# PlingPlong.net
KiCad netlist of a schematic drawn in EAGLE
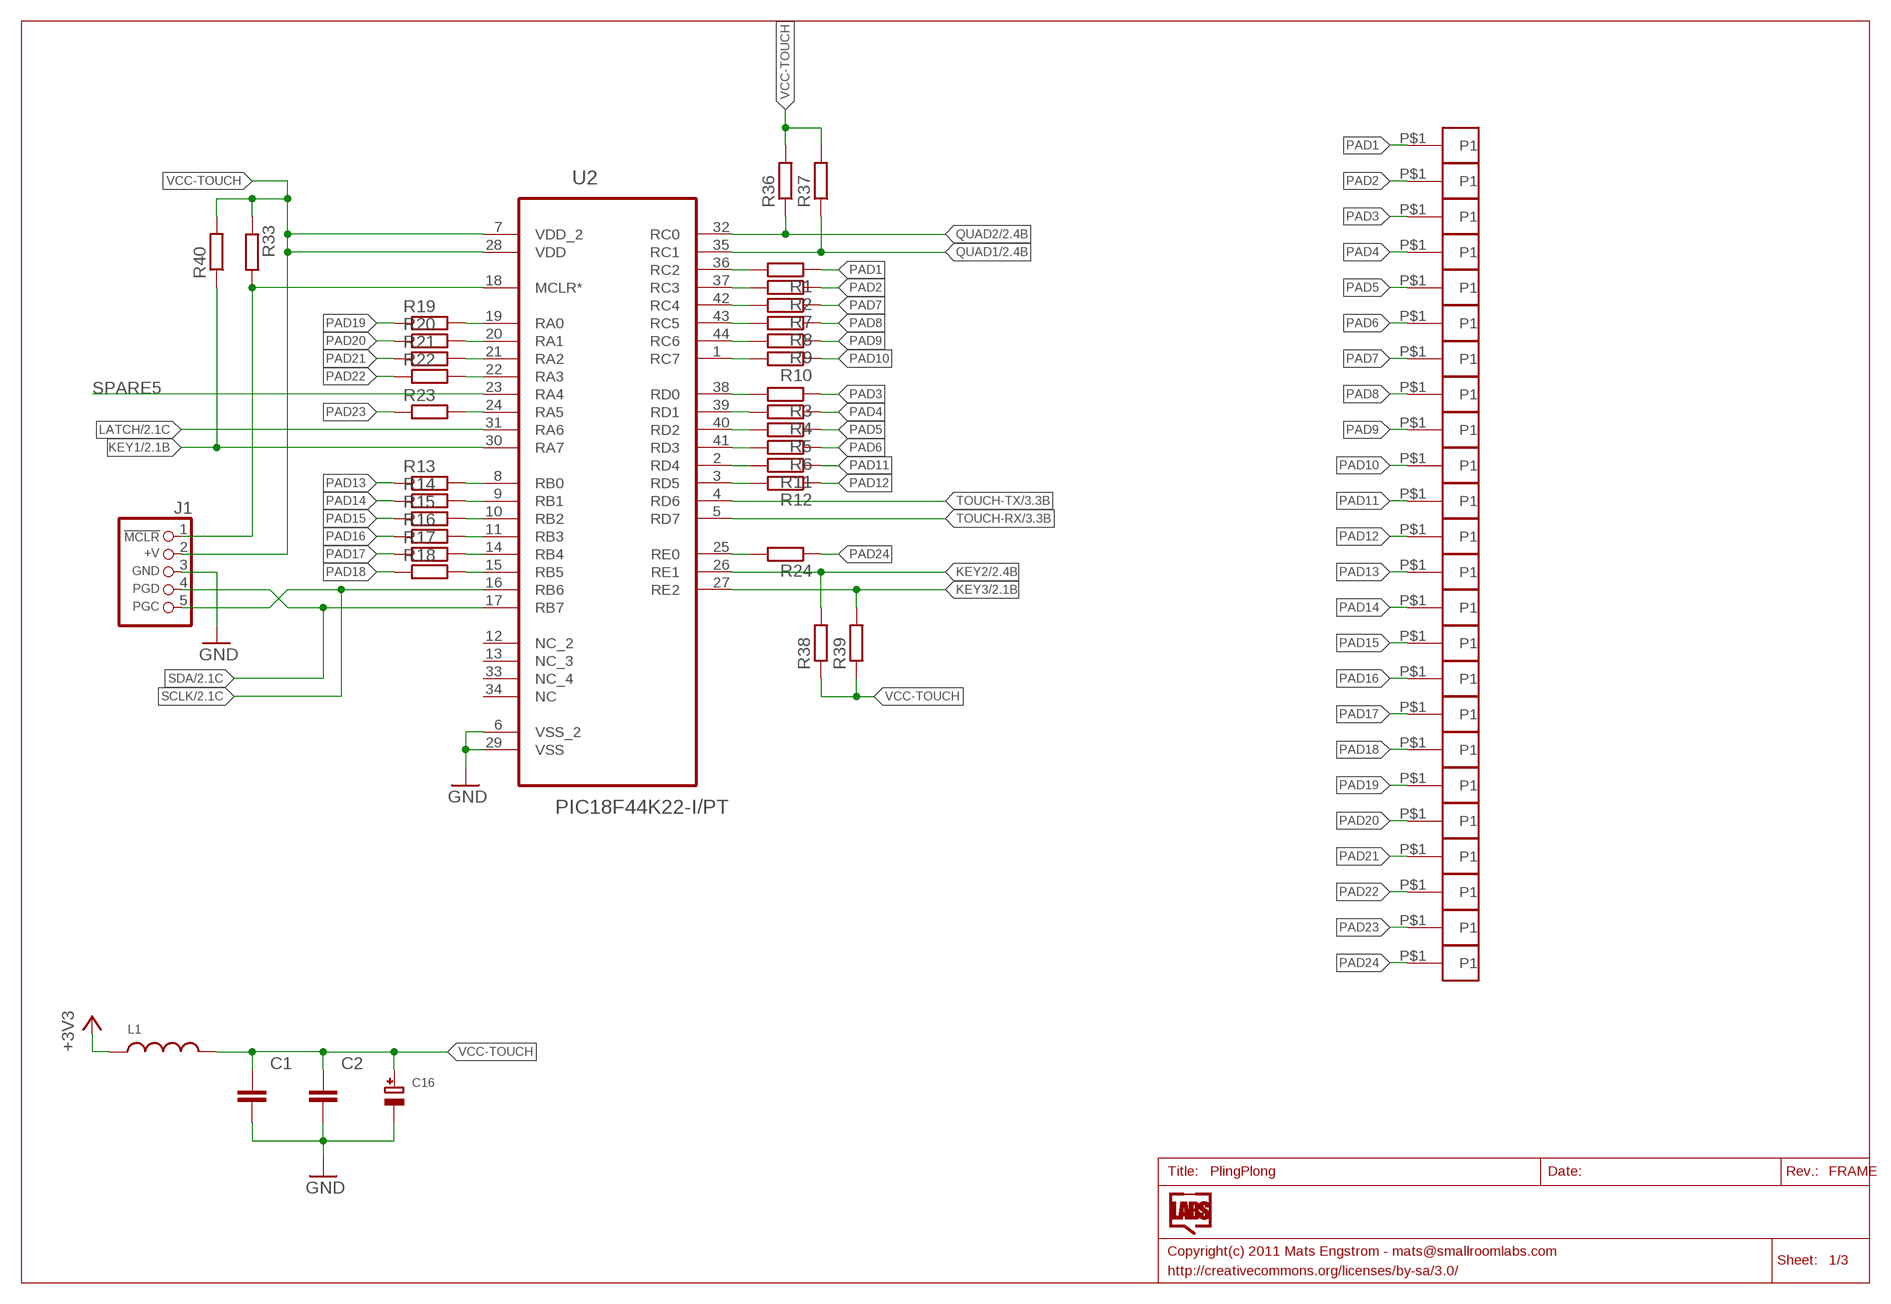
[diagram p0: schematic, sheet 1]
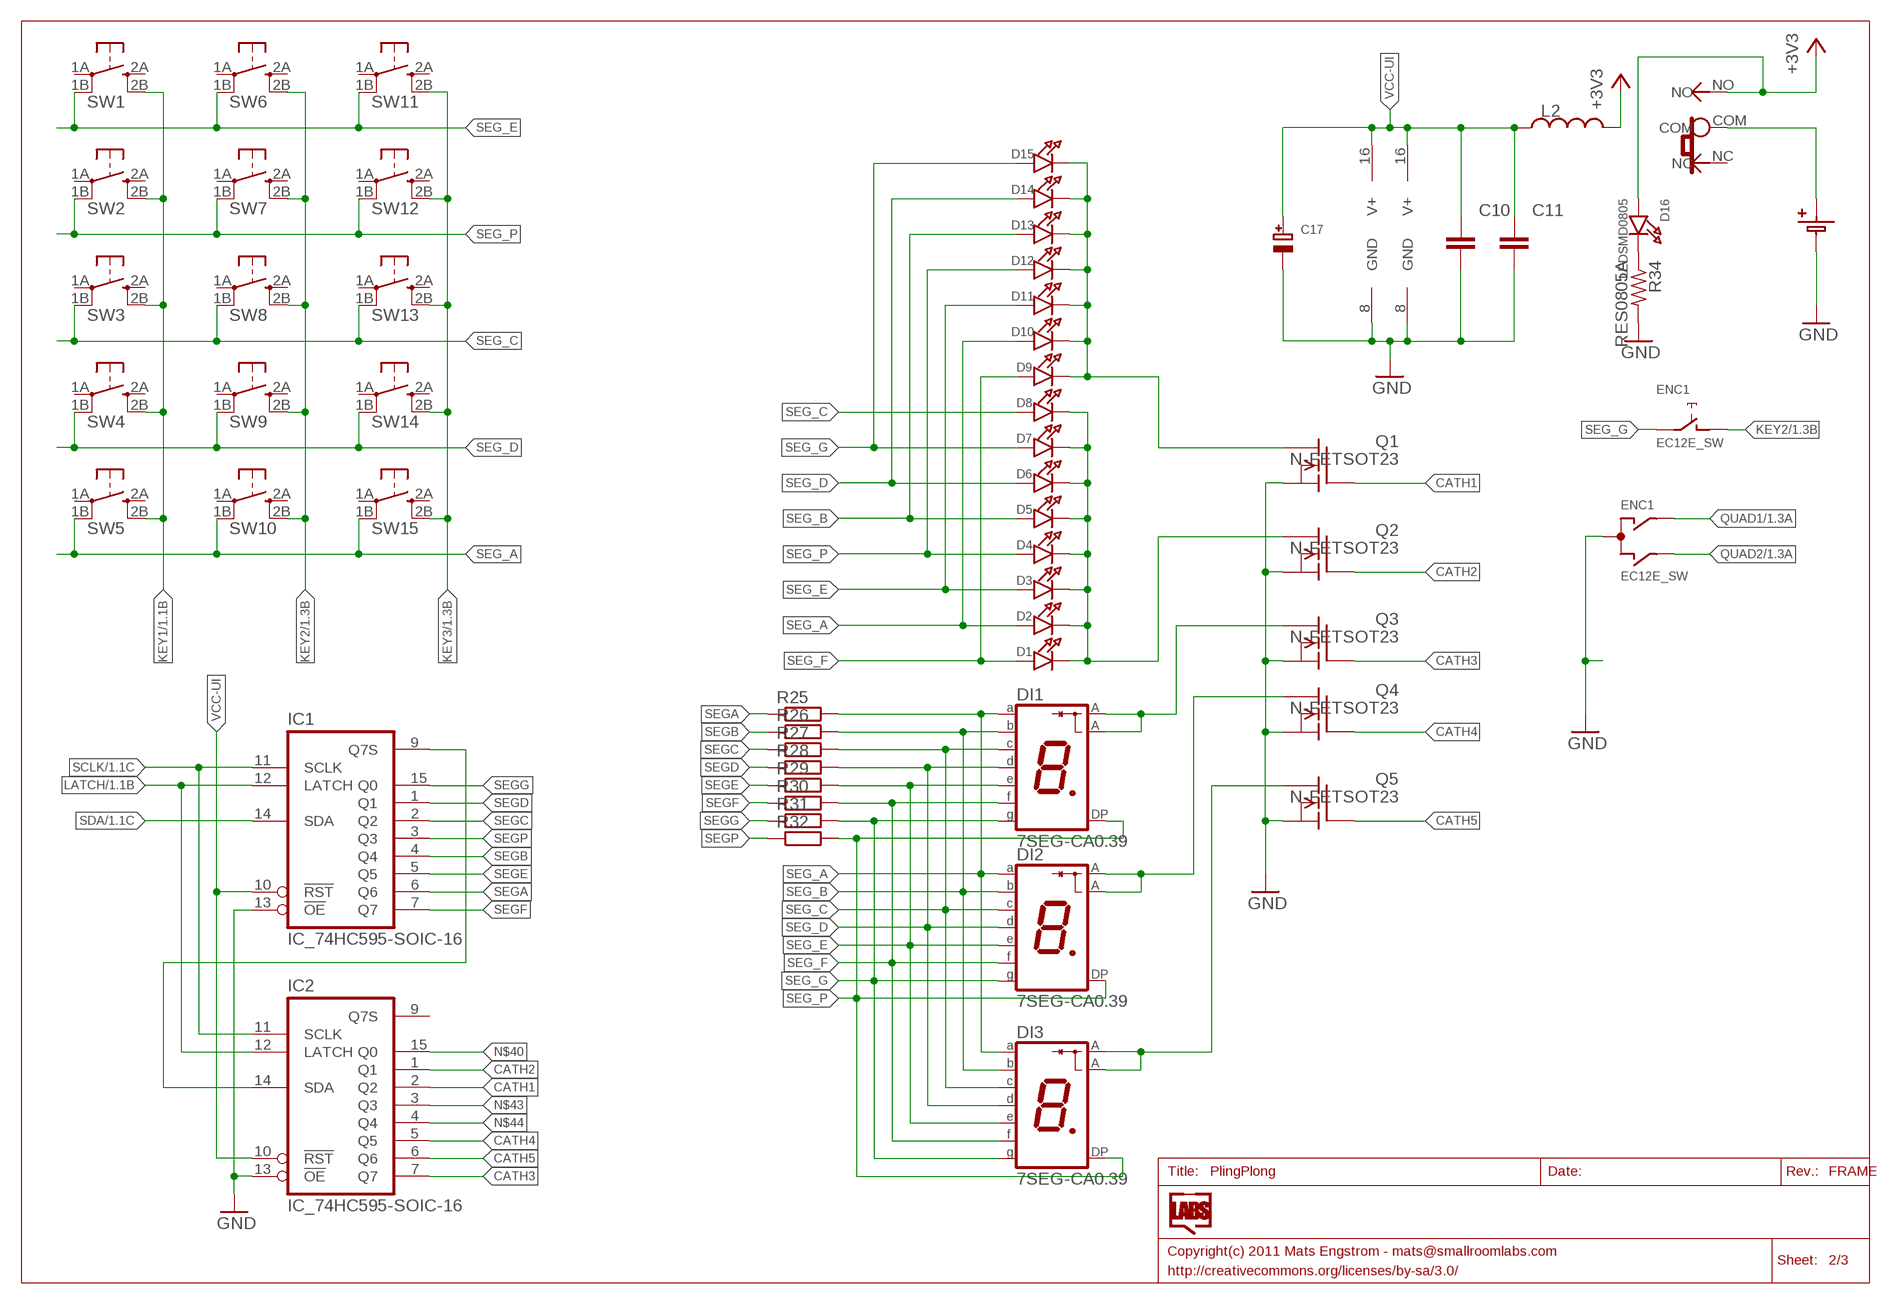
[diagram p1: schematic, sheet 2]
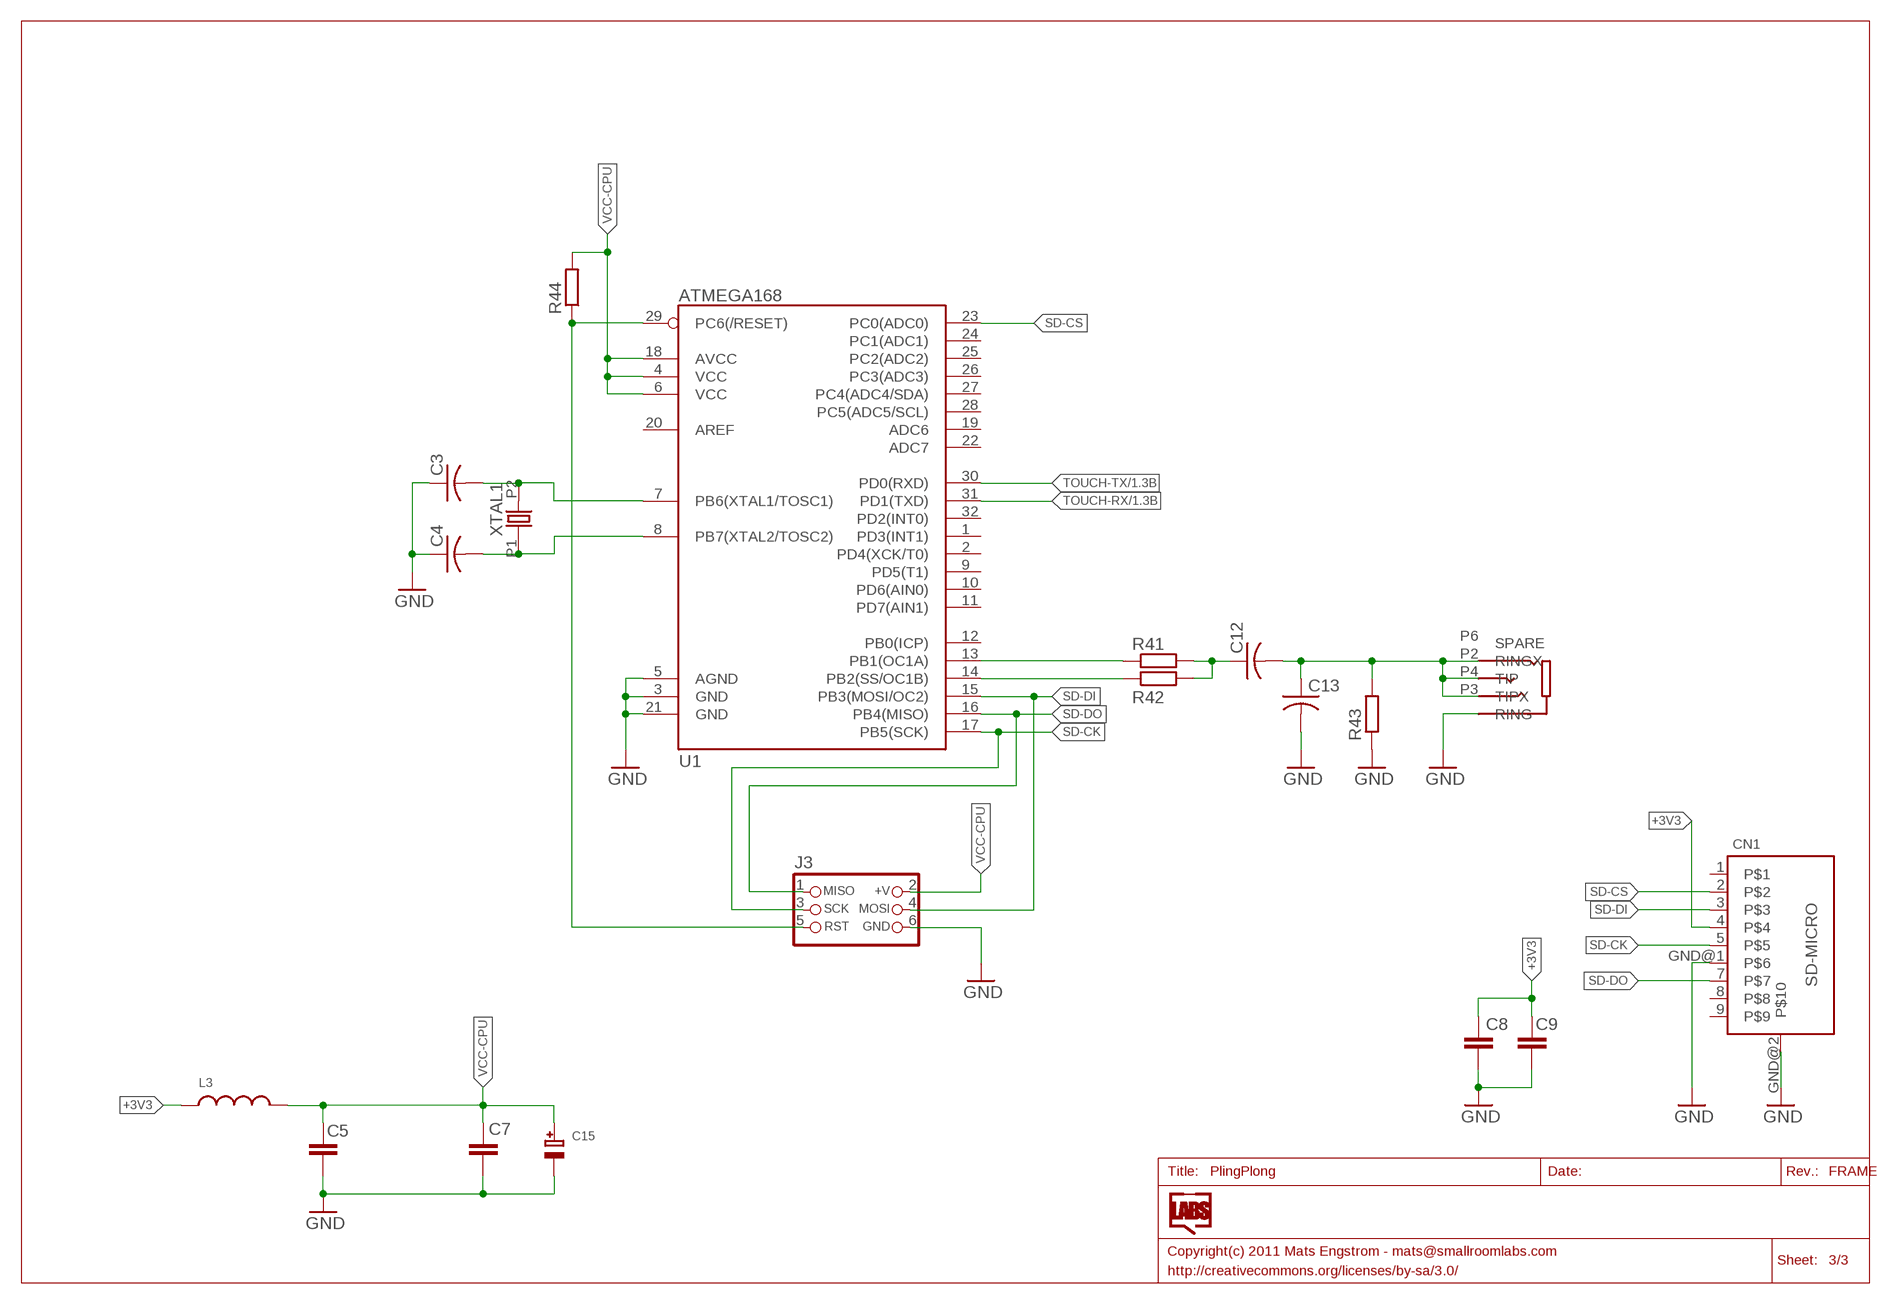
[diagram p2: schematic, sheet 3]

(export (version "E")
  (design (tool "Eeschema 10.0.6"))
  (components
    (comp (ref "C1")
      (value "CAPACITOR_NPOL-0805")
      (footprint "eagle-import:C805")
      (libsource (lib "eagle-import") (part "CAPACITOR_NPOL-0805"))
    )
    (comp (ref "C2")
      (value "CAPACITOR_NPOL-0805")
      (footprint "eagle-import:C805")
      (libsource (lib "eagle-import") (part "CAPACITOR_NPOL-0805"))
    )
    (comp (ref "C16")
      (value "CAP_TANTALUMD/7343_WAVE")
      (footprint "eagle-import:EIA7343-31_D-W")
      (libsource (lib "eagle-import") (part "CAP_TANTALUMD/7343_WAVE"))
    )
    (comp (ref "J1")
      (value "CON_HEADER_PRG_PIC_ICSPB")
      (footprint "eagle-import:HEADER_PRG_1X05_ICSP_B")
      (libsource (lib "eagle-import") (part "CON_HEADER_PRG_PIC_ICSPB"))
    )
    (comp (ref "L1")
      (value "INDUCTOR0805")
      (footprint "eagle-import:0805")
      (libsource (lib "eagle-import") (part "INDUCTOR0805"))
    )
    (comp (ref "P1")
      (value "PAD-NOSTOP")
      (footprint "eagle-import:PAD1X1NOSTOP")
      (libsource (lib "eagle-import") (part "PAD-NOSTOP"))
    )
    (comp (ref "P2")
      (value "PAD-NOSTOP")
      (footprint "eagle-import:PAD1X1NOSTOP")
      (libsource (lib "eagle-import") (part "PAD-NOSTOP"))
    )
    (comp (ref "P3")
      (value "PAD-NOSTOP")
      (footprint "eagle-import:PAD1X1NOSTOP")
      (libsource (lib "eagle-import") (part "PAD-NOSTOP"))
    )
    (comp (ref "P4")
      (value "PAD-NOSTOP")
      (footprint "eagle-import:PAD1X1NOSTOP")
      (libsource (lib "eagle-import") (part "PAD-NOSTOP"))
    )
    (comp (ref "P5")
      (value "PAD-NOSTOP")
      (footprint "eagle-import:PAD1X1NOSTOP")
      (libsource (lib "eagle-import") (part "PAD-NOSTOP"))
    )
    (comp (ref "P6")
      (value "PAD-NOSTOP")
      (footprint "eagle-import:PAD1X1NOSTOP")
      (libsource (lib "eagle-import") (part "PAD-NOSTOP"))
    )
    (comp (ref "P7")
      (value "PAD-NOSTOP")
      (footprint "eagle-import:PAD1X1NOSTOP")
      (libsource (lib "eagle-import") (part "PAD-NOSTOP"))
    )
    (comp (ref "P8")
      (value "PAD-NOSTOP")
      (footprint "eagle-import:PAD1X1NOSTOP")
      (libsource (lib "eagle-import") (part "PAD-NOSTOP"))
    )
    (comp (ref "P9")
      (value "PAD-NOSTOP")
      (footprint "eagle-import:PAD1X1NOSTOP")
      (libsource (lib "eagle-import") (part "PAD-NOSTOP"))
    )
    (comp (ref "P10")
      (value "PAD-NOSTOP")
      (footprint "eagle-import:PAD1X1NOSTOP")
      (libsource (lib "eagle-import") (part "PAD-NOSTOP"))
    )
    (comp (ref "P11")
      (value "PAD-NOSTOP")
      (footprint "eagle-import:PAD1X1NOSTOP")
      (libsource (lib "eagle-import") (part "PAD-NOSTOP"))
    )
    (comp (ref "P12")
      (value "PAD-NOSTOP")
      (footprint "eagle-import:PAD1X1NOSTOP")
      (libsource (lib "eagle-import") (part "PAD-NOSTOP"))
    )
    (comp (ref "P13")
      (value "PAD-NOSTOP")
      (footprint "eagle-import:PAD1X1NOSTOP")
      (libsource (lib "eagle-import") (part "PAD-NOSTOP"))
    )
    (comp (ref "P14")
      (value "PAD-NOSTOP")
      (footprint "eagle-import:PAD1X1NOSTOP")
      (libsource (lib "eagle-import") (part "PAD-NOSTOP"))
    )
    (comp (ref "P15")
      (value "PAD-NOSTOP")
      (footprint "eagle-import:PAD1X1NOSTOP")
      (libsource (lib "eagle-import") (part "PAD-NOSTOP"))
    )
    (comp (ref "P16")
      (value "PAD-NOSTOP")
      (footprint "eagle-import:PAD1X1NOSTOP")
      (libsource (lib "eagle-import") (part "PAD-NOSTOP"))
    )
    (comp (ref "P17")
      (value "PAD-NOSTOP")
      (footprint "eagle-import:PAD1X1NOSTOP")
      (libsource (lib "eagle-import") (part "PAD-NOSTOP"))
    )
    (comp (ref "P18")
      (value "PAD-NOSTOP")
      (footprint "eagle-import:PAD1X1NOSTOP")
      (libsource (lib "eagle-import") (part "PAD-NOSTOP"))
    )
    (comp (ref "P19")
      (value "PAD-NOSTOP")
      (footprint "eagle-import:PAD1X1NOSTOP")
      (libsource (lib "eagle-import") (part "PAD-NOSTOP"))
    )
    (comp (ref "P20")
      (value "PAD-NOSTOP")
      (footprint "eagle-import:PAD1X1NOSTOP")
      (libsource (lib "eagle-import") (part "PAD-NOSTOP"))
    )
    (comp (ref "P21")
      (value "PAD-NOSTOP")
      (footprint "eagle-import:PAD1X1NOSTOP")
      (libsource (lib "eagle-import") (part "PAD-NOSTOP"))
    )
    (comp (ref "P22")
      (value "PAD-NOSTOP")
      (footprint "eagle-import:PAD1X1NOSTOP")
      (libsource (lib "eagle-import") (part "PAD-NOSTOP"))
    )
    (comp (ref "P23")
      (value "PAD-NOSTOP")
      (footprint "eagle-import:PAD1X1NOSTOP")
      (libsource (lib "eagle-import") (part "PAD-NOSTOP"))
    )
    (comp (ref "P24")
      (value "PAD-NOSTOP")
      (footprint "eagle-import:PAD1X1NOSTOP")
      (libsource (lib "eagle-import") (part "PAD-NOSTOP"))
    )
    (comp (ref "R1")
      (value "R-EU_R0805W")
      (footprint "eagle-import:R0805W")
      (libsource (lib "eagle-import") (part "R-EU_R0805W"))
    )
    (comp (ref "R2")
      (value "R-EU_R0805W")
      (footprint "eagle-import:R0805W")
      (libsource (lib "eagle-import") (part "R-EU_R0805W"))
    )
    (comp (ref "R3")
      (value "R-EU_R0805W")
      (footprint "eagle-import:R0805W")
      (libsource (lib "eagle-import") (part "R-EU_R0805W"))
    )
    (comp (ref "R4")
      (value "R-EU_R0805W")
      (footprint "eagle-import:R0805W")
      (libsource (lib "eagle-import") (part "R-EU_R0805W"))
    )
    (comp (ref "R5")
      (value "R-EU_R0805W")
      (footprint "eagle-import:R0805W")
      (libsource (lib "eagle-import") (part "R-EU_R0805W"))
    )
    (comp (ref "R6")
      (value "R-EU_R0805W")
      (footprint "eagle-import:R0805W")
      (libsource (lib "eagle-import") (part "R-EU_R0805W"))
    )
    (comp (ref "R7")
      (value "R-EU_R0805W")
      (footprint "eagle-import:R0805W")
      (libsource (lib "eagle-import") (part "R-EU_R0805W"))
    )
    (comp (ref "R8")
      (value "R-EU_R0805W")
      (footprint "eagle-import:R0805W")
      (libsource (lib "eagle-import") (part "R-EU_R0805W"))
    )
    (comp (ref "R9")
      (value "R-EU_R0805W")
      (footprint "eagle-import:R0805W")
      (libsource (lib "eagle-import") (part "R-EU_R0805W"))
    )
    (comp (ref "R10")
      (value "R-EU_R0805W")
      (footprint "eagle-import:R0805W")
      (libsource (lib "eagle-import") (part "R-EU_R0805W"))
    )
    (comp (ref "R11")
      (value "R-EU_R0805W")
      (footprint "eagle-import:R0805W")
      (libsource (lib "eagle-import") (part "R-EU_R0805W"))
    )
    (comp (ref "R12")
      (value "R-EU_R0805W")
      (footprint "eagle-import:R0805W")
      (libsource (lib "eagle-import") (part "R-EU_R0805W"))
    )
    (comp (ref "R13")
      (value "R-EU_R0805W")
      (footprint "eagle-import:R0805W")
      (libsource (lib "eagle-import") (part "R-EU_R0805W"))
    )
    (comp (ref "R14")
      (value "R-EU_R0805W")
      (footprint "eagle-import:R0805W")
      (libsource (lib "eagle-import") (part "R-EU_R0805W"))
    )
    (comp (ref "R15")
      (value "R-EU_R0805W")
      (footprint "eagle-import:R0805W")
      (libsource (lib "eagle-import") (part "R-EU_R0805W"))
    )
    (comp (ref "R16")
      (value "R-EU_R0805W")
      (footprint "eagle-import:R0805W")
      (libsource (lib "eagle-import") (part "R-EU_R0805W"))
    )
    (comp (ref "R17")
      (value "R-EU_R0805W")
      (footprint "eagle-import:R0805W")
      (libsource (lib "eagle-import") (part "R-EU_R0805W"))
    )
    (comp (ref "R18")
      (value "R-EU_R0805W")
      (footprint "eagle-import:R0805W")
      (libsource (lib "eagle-import") (part "R-EU_R0805W"))
    )
    (comp (ref "R19")
      (value "R-EU_R0805W")
      (footprint "eagle-import:R0805W")
      (libsource (lib "eagle-import") (part "R-EU_R0805W"))
    )
    (comp (ref "R20")
      (value "R-EU_R0805W")
      (footprint "eagle-import:R0805W")
      (libsource (lib "eagle-import") (part "R-EU_R0805W"))
    )
    (comp (ref "R21")
      (value "R-EU_R0805W")
      (footprint "eagle-import:R0805W")
      (libsource (lib "eagle-import") (part "R-EU_R0805W"))
    )
    (comp (ref "R22")
      (value "R-EU_R0805W")
      (footprint "eagle-import:R0805W")
      (libsource (lib "eagle-import") (part "R-EU_R0805W"))
    )
    (comp (ref "R23")
      (value "R-EU_R0805W")
      (footprint "eagle-import:R0805W")
      (libsource (lib "eagle-import") (part "R-EU_R0805W"))
    )
    (comp (ref "R24")
      (value "R-EU_R0805W")
      (footprint "eagle-import:R0805W")
      (libsource (lib "eagle-import") (part "R-EU_R0805W"))
    )
    (comp (ref "R33")
      (value "R-EU_R0805W")
      (footprint "eagle-import:R0805W")
      (libsource (lib "eagle-import") (part "R-EU_R0805W"))
    )
    (comp (ref "R36")
      (value "R-EU_R0805W")
      (footprint "eagle-import:R0805W")
      (libsource (lib "eagle-import") (part "R-EU_R0805W"))
    )
    (comp (ref "R37")
      (value "R-EU_R0805W")
      (footprint "eagle-import:R0805W")
      (libsource (lib "eagle-import") (part "R-EU_R0805W"))
    )
    (comp (ref "R38")
      (value "R-EU_R0805W")
      (footprint "eagle-import:R0805W")
      (libsource (lib "eagle-import") (part "R-EU_R0805W"))
    )
    (comp (ref "R39")
      (value "R-EU_R0805W")
      (footprint "eagle-import:R0805W")
      (libsource (lib "eagle-import") (part "R-EU_R0805W"))
    )
    (comp (ref "R40")
      (value "R-EU_R0805W")
      (footprint "eagle-import:R0805W")
      (libsource (lib "eagle-import") (part "R-EU_R0805W"))
    )
    (comp (ref "U2")
      (value "PIC18F44K22-I/PT")
      (footprint "eagle-import:QFP80P1200X1200X120-44N")
      (libsource (lib "eagle-import") (part "PIC18F44K22-I/PT"))
    )
    (comp (ref "C3")
      (value "C-USC0805")
      (footprint "eagle-import:C0805")
      (libsource (lib "eagle-import") (part "C-USC0805"))
    )
    (comp (ref "C4")
      (value "C-USC0805")
      (footprint "eagle-import:C0805")
      (libsource (lib "eagle-import") (part "C-USC0805"))
    )
    (comp (ref "C5")
      (value "CAPACITOR_NPOL-0805")
      (footprint "eagle-import:C805")
      (libsource (lib "eagle-import") (part "CAPACITOR_NPOL-0805"))
    )
    (comp (ref "C7")
      (value "CAPACITOR_NPOL-0805")
      (footprint "eagle-import:C805")
      (libsource (lib "eagle-import") (part "CAPACITOR_NPOL-0805"))
    )
    (comp (ref "C8")
      (value "CAPACITOR_NPOL-0805")
      (footprint "eagle-import:C805")
      (libsource (lib "eagle-import") (part "CAPACITOR_NPOL-0805"))
    )
    (comp (ref "C9")
      (value "CAPACITOR_NPOL-0805")
      (footprint "eagle-import:C805")
      (libsource (lib "eagle-import") (part "CAPACITOR_NPOL-0805"))
    )
    (comp (ref "C12")
      (value "C-USC1206")
      (footprint "eagle-import:C1206")
      (libsource (lib "eagle-import") (part "C-USC1206"))
    )
    (comp (ref "C13")
      (value "C-USC0805")
      (footprint "eagle-import:C0805")
      (libsource (lib "eagle-import") (part "C-USC0805"))
    )
    (comp (ref "C15")
      (value "CAP_TANTALUMD/7343_WAVE")
      (footprint "eagle-import:EIA7343-31_D-W")
      (libsource (lib "eagle-import") (part "CAP_TANTALUMD/7343_WAVE"))
    )
    (comp (ref "CN1")
      (value "SD-MICRO")
      (footprint "eagle-import:MICROSD-TFP09")
      (libsource (lib "eagle-import") (part "SD-MICRO"))
    )
    (comp (ref "J3")
      (value "CON_HEADER_PRG_AVR_ICSP")
      (footprint "eagle-import:HEADER_PRG_2X03")
      (libsource (lib "eagle-import") (part "CON_HEADER_PRG_AVR_ICSP"))
    )
    (comp (ref "L3")
      (value "INDUCTOR0805")
      (footprint "eagle-import:0805")
      (libsource (lib "eagle-import") (part "INDUCTOR0805"))
    )
    (comp (ref "R41")
      (value "R-EU_R0805W")
      (footprint "eagle-import:R0805W")
      (libsource (lib "eagle-import") (part "R-EU_R0805W"))
    )
    (comp (ref "R42")
      (value "R-EU_R0805W")
      (footprint "eagle-import:R0805W")
      (libsource (lib "eagle-import") (part "R-EU_R0805W"))
    )
    (comp (ref "R43")
      (value "R-EU_R0805W")
      (footprint "eagle-import:R0805W")
      (libsource (lib "eagle-import") (part "R-EU_R0805W"))
    )
    (comp (ref "R44")
      (value "R-EU_R0805W")
      (footprint "eagle-import:R0805W")
      (libsource (lib "eagle-import") (part "R-EU_R0805W"))
    )
    (comp (ref "U$2")
      (value "JACK4-PJ320")
      (footprint "eagle-import:PJ-320E")
      (libsource (lib "eagle-import") (part "JACK4-PJ320"))
    )
    (comp (ref "U1")
      (value "ATMEGA168")
      (footprint "eagle-import:TQFP32-08")
      (libsource (lib "eagle-import") (part "ATMEGA168"))
    )
    (comp (ref "XTAL1")
      (value "OSC-XTAL-HC-49U-PTH")
      (footprint "eagle-import:HC-49U-PTH")
      (libsource (lib "eagle-import") (part "OSC-XTAL-HC-49U-PTH"))
    )
    (comp (ref "BA1")
      (value "BATTERY1-123PIN")
      (footprint "eagle-import:BATTERY-CR123A-PINS")
      (libsource (lib "eagle-import") (part "BATTERY1-123PIN"))
    )
    (comp (ref "C10")
      (value "CAPACITOR_NPOL-0805")
      (footprint "eagle-import:C805")
      (libsource (lib "eagle-import") (part "CAPACITOR_NPOL-0805"))
    )
    (comp (ref "C11")
      (value "CAPACITOR_NPOL-0805")
      (footprint "eagle-import:C805")
      (libsource (lib "eagle-import") (part "CAPACITOR_NPOL-0805"))
    )
    (comp (ref "C17")
      (value "CAP_TANTALUMD/7343_WAVE")
      (footprint "eagle-import:EIA7343-31_D-W")
      (libsource (lib "eagle-import") (part "CAP_TANTALUMD/7343_WAVE"))
    )
    (comp (ref "D1")
      (value "LED3MM")
      (footprint "eagle-import:LED3MM")
      (libsource (lib "eagle-import") (part "LED3MM"))
    )
    (comp (ref "D2")
      (value "LED3MM")
      (footprint "eagle-import:LED3MM")
      (libsource (lib "eagle-import") (part "LED3MM"))
    )
    (comp (ref "D3")
      (value "LED3MM")
      (footprint "eagle-import:LED3MM")
      (libsource (lib "eagle-import") (part "LED3MM"))
    )
    (comp (ref "D4")
      (value "LED3MM")
      (footprint "eagle-import:LED3MM")
      (libsource (lib "eagle-import") (part "LED3MM"))
    )
    (comp (ref "D5")
      (value "LED3MM")
      (footprint "eagle-import:LED3MM")
      (libsource (lib "eagle-import") (part "LED3MM"))
    )
    (comp (ref "D6")
      (value "LED3MM")
      (footprint "eagle-import:LED3MM")
      (libsource (lib "eagle-import") (part "LED3MM"))
    )
    (comp (ref "D7")
      (value "LED3MM")
      (footprint "eagle-import:LED3MM")
      (libsource (lib "eagle-import") (part "LED3MM"))
    )
    (comp (ref "D8")
      (value "LED3MM")
      (footprint "eagle-import:LED3MM")
      (libsource (lib "eagle-import") (part "LED3MM"))
    )
    (comp (ref "D9")
      (value "LED3MM")
      (footprint "eagle-import:LED3MM")
      (libsource (lib "eagle-import") (part "LED3MM"))
    )
    (comp (ref "D10")
      (value "LED3MM")
      (footprint "eagle-import:LED3MM")
      (libsource (lib "eagle-import") (part "LED3MM"))
    )
    (comp (ref "D11")
      (value "LED3MM")
      (footprint "eagle-import:LED3MM")
      (libsource (lib "eagle-import") (part "LED3MM"))
    )
    (comp (ref "D12")
      (value "LED3MM")
      (footprint "eagle-import:LED3MM")
      (libsource (lib "eagle-import") (part "LED3MM"))
    )
    (comp (ref "D13")
      (value "LED3MM")
      (footprint "eagle-import:LED3MM")
      (libsource (lib "eagle-import") (part "LED3MM"))
    )
    (comp (ref "D14")
      (value "LED3MM")
      (footprint "eagle-import:LED3MM")
      (libsource (lib "eagle-import") (part "LED3MM"))
    )
    (comp (ref "D15")
      (value "LED3MM")
      (footprint "eagle-import:LED3MM")
      (libsource (lib "eagle-import") (part "LED3MM"))
    )
    (comp (ref "D16")
      (value "LEDSMD0805")
      (footprint "eagle-import:CHIPLED_0805")
      (libsource (lib "eagle-import") (part "LEDSMD0805"))
    )
    (comp (ref "DI1")
      (value "7SEG-CA0.39")
      (footprint "eagle-import:LG3911")
      (libsource (lib "eagle-import") (part "7SEG-CA0.39"))
    )
    (comp (ref "DI2")
      (value "7SEG-CA0.39")
      (footprint "eagle-import:LG3911")
      (libsource (lib "eagle-import") (part "7SEG-CA0.39"))
    )
    (comp (ref "DI3")
      (value "7SEG-CA0.39")
      (footprint "eagle-import:LG3911")
      (libsource (lib "eagle-import") (part "7SEG-CA0.39"))
    )
    (comp (ref "ENC1")
      (value "EC12E_SW")
      (footprint "eagle-import:ALPS_EC12E_SW")
      (fields (field (name "MPN") "EC12E2424407"))
      (libsource (lib "eagle-import") (part "EC12E_SW"))
    )
    (comp (ref "IC1")
      (value "IC_74HC595-SOIC-16")
      (footprint "eagle-import:SOIC-16")
      (libsource (lib "eagle-import") (part "IC_74HC595-SOIC-16"))
    )
    (comp (ref "IC2")
      (value "IC_74HC595-SOIC-16")
      (footprint "eagle-import:SOIC-16")
      (libsource (lib "eagle-import") (part "IC_74HC595-SOIC-16"))
    )
    (comp (ref "L2")
      (value "INDUCTOR0805")
      (footprint "eagle-import:0805")
      (libsource (lib "eagle-import") (part "INDUCTOR0805"))
    )
    (comp (ref "Q1")
      (value "N-FETSOT23")
      (footprint "eagle-import:SOT23")
      (libsource (lib "eagle-import") (part "N-FETSOT23"))
    )
    (comp (ref "Q2")
      (value "N-FETSOT23")
      (footprint "eagle-import:SOT23")
      (libsource (lib "eagle-import") (part "N-FETSOT23"))
    )
    (comp (ref "Q3")
      (value "N-FETSOT23")
      (footprint "eagle-import:SOT23")
      (libsource (lib "eagle-import") (part "N-FETSOT23"))
    )
    (comp (ref "Q4")
      (value "N-FETSOT23")
      (footprint "eagle-import:SOT23")
      (libsource (lib "eagle-import") (part "N-FETSOT23"))
    )
    (comp (ref "Q5")
      (value "N-FETSOT23")
      (footprint "eagle-import:SOT23")
      (libsource (lib "eagle-import") (part "N-FETSOT23"))
    )
    (comp (ref "R25")
      (value "R-EU_R0805W")
      (footprint "eagle-import:R0805W")
      (libsource (lib "eagle-import") (part "R-EU_R0805W"))
    )
    (comp (ref "R26")
      (value "R-EU_R0805W")
      (footprint "eagle-import:R0805W")
      (libsource (lib "eagle-import") (part "R-EU_R0805W"))
    )
    (comp (ref "R27")
      (value "R-EU_R0805W")
      (footprint "eagle-import:R0805W")
      (libsource (lib "eagle-import") (part "R-EU_R0805W"))
    )
    (comp (ref "R28")
      (value "R-EU_R0805W")
      (footprint "eagle-import:R0805W")
      (libsource (lib "eagle-import") (part "R-EU_R0805W"))
    )
    (comp (ref "R29")
      (value "R-EU_R0805W")
      (footprint "eagle-import:R0805W")
      (libsource (lib "eagle-import") (part "R-EU_R0805W"))
    )
    (comp (ref "R30")
      (value "R-EU_R0805W")
      (footprint "eagle-import:R0805W")
      (libsource (lib "eagle-import") (part "R-EU_R0805W"))
    )
    (comp (ref "R31")
      (value "R-EU_R0805W")
      (footprint "eagle-import:R0805W")
      (libsource (lib "eagle-import") (part "R-EU_R0805W"))
    )
    (comp (ref "R32")
      (value "R-EU_R0805W")
      (footprint "eagle-import:R0805W")
      (libsource (lib "eagle-import") (part "R-EU_R0805W"))
    )
    (comp (ref "R34")
      (value "RES0805A")
      (footprint "eagle-import:R0805A")
      (libsource (lib "eagle-import") (part "RES0805A"))
    )
    (comp (ref "SW1")
      (value "TACTILETACT-6X6-PTH")
      (footprint "eagle-import:TACTILE-PTH")
      (libsource (lib "eagle-import") (part "TACTILETACT-6X6-PTH"))
    )
    (comp (ref "SW2")
      (value "TACTILETACT-6X6-PTH")
      (footprint "eagle-import:TACTILE-PTH")
      (libsource (lib "eagle-import") (part "TACTILETACT-6X6-PTH"))
    )
    (comp (ref "SW3")
      (value "TACTILETACT-6X6-PTH")
      (footprint "eagle-import:TACTILE-PTH")
      (libsource (lib "eagle-import") (part "TACTILETACT-6X6-PTH"))
    )
    (comp (ref "SW4")
      (value "TACTILETACT-6X6-PTH")
      (footprint "eagle-import:TACTILE-PTH")
      (libsource (lib "eagle-import") (part "TACTILETACT-6X6-PTH"))
    )
    (comp (ref "SW5")
      (value "TACTILETACT-6X6-PTH")
      (footprint "eagle-import:TACTILE-PTH")
      (libsource (lib "eagle-import") (part "TACTILETACT-6X6-PTH"))
    )
    (comp (ref "SW6")
      (value "TACTILETACT-6X6-PTH")
      (footprint "eagle-import:TACTILE-PTH")
      (libsource (lib "eagle-import") (part "TACTILETACT-6X6-PTH"))
    )
    (comp (ref "SW7")
      (value "TACTILETACT-6X6-PTH")
      (footprint "eagle-import:TACTILE-PTH")
      (libsource (lib "eagle-import") (part "TACTILETACT-6X6-PTH"))
    )
    (comp (ref "SW8")
      (value "TACTILETACT-6X6-PTH")
      (footprint "eagle-import:TACTILE-PTH")
      (libsource (lib "eagle-import") (part "TACTILETACT-6X6-PTH"))
    )
    (comp (ref "SW9")
      (value "TACTILETACT-6X6-PTH")
      (footprint "eagle-import:TACTILE-PTH")
      (libsource (lib "eagle-import") (part "TACTILETACT-6X6-PTH"))
    )
    (comp (ref "SW10")
      (value "TACTILETACT-6X6-PTH")
      (footprint "eagle-import:TACTILE-PTH")
      (libsource (lib "eagle-import") (part "TACTILETACT-6X6-PTH"))
    )
    (comp (ref "SW11")
      (value "TACTILETACT-6X6-PTH")
      (footprint "eagle-import:TACTILE-PTH")
      (libsource (lib "eagle-import") (part "TACTILETACT-6X6-PTH"))
    )
    (comp (ref "SW12")
      (value "TACTILETACT-6X6-PTH")
      (footprint "eagle-import:TACTILE-PTH")
      (libsource (lib "eagle-import") (part "TACTILETACT-6X6-PTH"))
    )
    (comp (ref "SW13")
      (value "TACTILETACT-6X6-PTH")
      (footprint "eagle-import:TACTILE-PTH")
      (libsource (lib "eagle-import") (part "TACTILETACT-6X6-PTH"))
    )
    (comp (ref "SW14")
      (value "TACTILETACT-6X6-PTH")
      (footprint "eagle-import:TACTILE-PTH")
      (libsource (lib "eagle-import") (part "TACTILETACT-6X6-PTH"))
    )
    (comp (ref "SW15")
      (value "TACTILETACT-6X6-PTH")
      (footprint "eagle-import:TACTILE-PTH")
      (libsource (lib "eagle-import") (part "TACTILETACT-6X6-PTH"))
    )
    (comp (ref "SW16")
      (value "SLIDESWITCH-PCM12")
      (footprint "eagle-import:PCM12")
      (libsource (lib "eagle-import") (part "SLIDESWITCH-PCM12"))
    )
  )
  (nets
    (net (code "1") (name "+3V3") (class "Default")
      (node (ref "C8") (pin "1") (pinfunction "1_1") (pintype "passive"))
      (node (ref "C9") (pin "1") (pinfunction "1_1") (pintype "passive"))
      (node (ref "CN1") (pin "4") (pinfunction "P$4_4") (pintype "bidirectional"))
      (node (ref "D16") (pin "A") (pinfunction "A_A") (pintype "passive"))
      (node (ref "L1") (pin "1") (pinfunction "1_1") (pintype "passive"))
      (node (ref "L2") (pin "2") (pinfunction "2_2") (pintype "passive"))
      (node (ref "L3") (pin "1") (pinfunction "1_1") (pintype "passive"))
      (node (ref "SW16") (pin "NO") (pinfunction "NO_NO") (pintype "bidirectional"))
    )
    (net (code "2") (name "CATH1") (class "Default")
      (node (ref "IC2") (pin "2") (pinfunction "Q2_2") (pintype "output"))
      (node (ref "Q1") (pin "1") (pinfunction "G_1") (pintype "passive"))
    )
    (net (code "3") (name "CATH2") (class "Default")
      (node (ref "IC2") (pin "1") (pinfunction "Q1_1") (pintype "output"))
      (node (ref "Q2") (pin "1") (pinfunction "G_1") (pintype "passive"))
    )
    (net (code "4") (name "CATH3") (class "Default")
      (node (ref "IC2") (pin "7") (pinfunction "Q7_7") (pintype "output"))
      (node (ref "Q3") (pin "1") (pinfunction "G_1") (pintype "passive"))
    )
    (net (code "5") (name "CATH4") (class "Default")
      (node (ref "IC2") (pin "5") (pinfunction "Q5_5") (pintype "output"))
      (node (ref "Q4") (pin "1") (pinfunction "G_1") (pintype "passive"))
    )
    (net (code "6") (name "CATH5") (class "Default")
      (node (ref "IC2") (pin "6") (pinfunction "Q6_6") (pintype "output"))
      (node (ref "Q5") (pin "1") (pinfunction "G_1") (pintype "passive"))
    )
    (net (code "7") (name "GND") (class "Default")
      (node (ref "BA1") (pin "NEG") (pinfunction "NEG_NEG") (pintype "power_in"))
      (node (ref "C1") (pin "2") (pinfunction "2_2") (pintype "passive"))
      (node (ref "C10") (pin "2") (pinfunction "2_2") (pintype "passive"))
      (node (ref "C11") (pin "2") (pinfunction "2_2") (pintype "passive"))
      (node (ref "C13") (pin "2") (pinfunction "2_2") (pintype "passive"))
      (node (ref "C15") (pin "-") (pinfunction "-_-") (pintype "passive"))
      (node (ref "C16") (pin "-") (pinfunction "-_-") (pintype "passive"))
      (node (ref "C17") (pin "-") (pinfunction "-_-") (pintype "passive"))
      (node (ref "C2") (pin "2") (pinfunction "2_2") (pintype "passive"))
      (node (ref "C3") (pin "1") (pinfunction "1_1") (pintype "passive"))
      (node (ref "C4") (pin "1") (pinfunction "1_1") (pintype "passive"))
      (node (ref "C5") (pin "2") (pinfunction "2_2") (pintype "passive"))
      (node (ref "C7") (pin "2") (pinfunction "2_2") (pintype "passive"))
      (node (ref "C8") (pin "2") (pinfunction "2_2") (pintype "passive"))
      (node (ref "C9") (pin "2") (pinfunction "2_2") (pintype "passive"))
      (node (ref "CN1") (pin "GND@1") (pinfunction "P$6_GND@1") (pintype "bidirectional"))
      (node (ref "CN1") (pin "GND@2") (pinfunction "P$10_GND@2") (pintype "bidirectional"))
      (node (ref "ENC1") (pin "C") (pinfunction "C_C") (pintype "passive"))
      (node (ref "IC1") (pin "13") (pinfunction "~{OE}_13") (pintype "input"))
      (node (ref "IC1") (pin "8") (pinfunction "GND_8") (pintype "power_in"))
      (node (ref "IC2") (pin "13") (pinfunction "~{OE}_13") (pintype "input"))
      (node (ref "IC2") (pin "8") (pinfunction "GND_8") (pintype "power_in"))
      (node (ref "J1") (pin "3") (pinfunction "GND_3") (pintype "passive"))
      (node (ref "J3") (pin "6") (pinfunction "GND_6") (pintype "passive"))
      (node (ref "Q1") (pin "2") (pinfunction "S_2") (pintype "passive"))
      (node (ref "Q2") (pin "2") (pinfunction "S_2") (pintype "passive"))
      (node (ref "Q3") (pin "2") (pinfunction "S_2") (pintype "passive"))
      (node (ref "Q4") (pin "2") (pinfunction "S_2") (pintype "passive"))
      (node (ref "Q5") (pin "2") (pinfunction "S_2") (pintype "passive"))
      (node (ref "R34") (pin "2") (pinfunction "2_2") (pintype "passive"))
      (node (ref "R43") (pin "1") (pinfunction "1_1") (pintype "passive"))
      (node (ref "U$2") (pin "P5") (pinfunction "RING_P5") (pintype "bidirectional"))
      (node (ref "U1") (pin "21") (pinfunction "GND_21") (pintype "bidirectional"))
      (node (ref "U1") (pin "3") (pinfunction "GND_3") (pintype "bidirectional"))
      (node (ref "U1") (pin "5") (pinfunction "AGND_5") (pintype "bidirectional"))
      (node (ref "U2") (pin "29") (pinfunction "VSS_29") (pintype "power_in"))
      (node (ref "U2") (pin "6") (pinfunction "VSS_2_6") (pintype "power_in"))
    )
    (net (code "8") (name "KEY1") (class "Default")
      (node (ref "R40") (pin "1") (pinfunction "1_1") (pintype "passive"))
      (node (ref "SW1") (pin "2B") (pinfunction "2B_2B") (pintype "passive"))
      (node (ref "SW2") (pin "2B") (pinfunction "2B_2B") (pintype "passive"))
      (node (ref "SW3") (pin "2B") (pinfunction "2B_2B") (pintype "passive"))
      (node (ref "SW4") (pin "2B") (pinfunction "2B_2B") (pintype "passive"))
      (node (ref "SW5") (pin "2B") (pinfunction "2B_2B") (pintype "passive"))
      (node (ref "U2") (pin "30") (pinfunction "RA7_30") (pintype "bidirectional"))
    )
    (net (code "9") (name "KEY2") (class "Default")
      (node (ref "ENC1") (pin "D") (pinfunction "1_D") (pintype "passive"))
      (node (ref "R38") (pin "2") (pinfunction "2_2") (pintype "passive"))
      (node (ref "SW10") (pin "2B") (pinfunction "2B_2B") (pintype "passive"))
      (node (ref "SW6") (pin "2B") (pinfunction "2B_2B") (pintype "passive"))
      (node (ref "SW7") (pin "2B") (pinfunction "2B_2B") (pintype "passive"))
      (node (ref "SW8") (pin "2B") (pinfunction "2B_2B") (pintype "passive"))
      (node (ref "SW9") (pin "2B") (pinfunction "2B_2B") (pintype "passive"))
      (node (ref "U2") (pin "26") (pinfunction "RE1_26") (pintype "bidirectional"))
    )
    (net (code "10") (name "KEY3") (class "Default")
      (node (ref "R39") (pin "2") (pinfunction "2_2") (pintype "passive"))
      (node (ref "SW11") (pin "2B") (pinfunction "2B_2B") (pintype "passive"))
      (node (ref "SW12") (pin "2B") (pinfunction "2B_2B") (pintype "passive"))
      (node (ref "SW13") (pin "2B") (pinfunction "2B_2B") (pintype "passive"))
      (node (ref "SW14") (pin "2B") (pinfunction "2B_2B") (pintype "passive"))
      (node (ref "SW15") (pin "2B") (pinfunction "2B_2B") (pintype "passive"))
      (node (ref "U2") (pin "27") (pinfunction "RE2_27") (pintype "bidirectional"))
    )
    (net (code "11") (name "LATCH") (class "Default")
      (node (ref "IC1") (pin "12") (pinfunction "LATCH_12") (pintype "input"))
      (node (ref "IC2") (pin "12") (pinfunction "LATCH_12") (pintype "input"))
      (node (ref "U2") (pin "31") (pinfunction "RA6_31") (pintype "bidirectional"))
    )
    (net (code "12") (name "N$40") (class "Default")
      (node (ref "IC2") (pin "15") (pinfunction "Q0_15") (pintype "output"))
    )
    (net (code "13") (name "N$43") (class "Default")
      (node (ref "IC2") (pin "3") (pinfunction "Q3_3") (pintype "output"))
    )
    (net (code "14") (name "N$44") (class "Default")
      (node (ref "IC2") (pin "4") (pinfunction "Q4_4") (pintype "output"))
    )
    (net (code "15") (name "Net-(BA1-POS1)") (class "Default")
      (node (ref "BA1") (pin "POS") (pinfunction "POS1_POS") (pintype "power_in"))
      (node (ref "SW16") (pin "COM") (pinfunction "COM_COM") (pintype "bidirectional"))
    )
    (net (code "16") (name "Net-(C12-Pad1)") (class "Default")
      (node (ref "C12") (pin "1") (pinfunction "1_1") (pintype "passive"))
      (node (ref "R41") (pin "2") (pinfunction "2_2") (pintype "passive"))
      (node (ref "R42") (pin "2") (pinfunction "2_2") (pintype "passive"))
    )
    (net (code "17") (name "Net-(D16-PadC)") (class "Default")
      (node (ref "D16") (pin "C") (pinfunction "C_C") (pintype "passive"))
      (node (ref "R34") (pin "1") (pinfunction "1_1") (pintype "passive"))
    )
    (net (code "18") (name "Net-(IC1A-Q7S)") (class "Default")
      (node (ref "IC1") (pin "9") (pinfunction "Q7S_9") (pintype "output"))
      (node (ref "IC2") (pin "14") (pinfunction "SDA_14") (pintype "input"))
    )
    (net (code "19") (name "Net-(J1-{slash}MCLR)") (class "Default")
      (node (ref "J1") (pin "1") (pinfunction "/MCLR_1") (pintype "passive"))
      (node (ref "R33") (pin "2") (pinfunction "2_2") (pintype "passive"))
      (node (ref "U2") (pin "18") (pinfunction "MCLR*_18") (pintype "input"))
    )
    (net (code "20") (name "Net-(J3-RST)") (class "Default")
      (node (ref "J3") (pin "5") (pinfunction "RST_5") (pintype "passive"))
      (node (ref "R44") (pin "1") (pinfunction "1_1") (pintype "passive"))
      (node (ref "U1") (pin "29") (pinfunction "PC6(/RESET)_29") (pintype "bidirectional"))
    )
    (net (code "21") (name "Net-(Q1-D)") (class "Default")
      (node (ref "D10") (pin "C") (pinfunction "C_C") (pintype "passive"))
      (node (ref "D11") (pin "C") (pinfunction "C_C") (pintype "passive"))
      (node (ref "D12") (pin "C") (pinfunction "C_C") (pintype "passive"))
      (node (ref "D13") (pin "C") (pinfunction "C_C") (pintype "passive"))
      (node (ref "D14") (pin "C") (pinfunction "C_C") (pintype "passive"))
      (node (ref "D15") (pin "C") (pinfunction "C_C") (pintype "passive"))
      (node (ref "D9") (pin "C") (pinfunction "C_C") (pintype "passive"))
      (node (ref "Q1") (pin "3") (pinfunction "D_3") (pintype "passive"))
    )
    (net (code "22") (name "Net-(Q2-D)") (class "Default")
      (node (ref "D1") (pin "C") (pinfunction "C_C") (pintype "passive"))
      (node (ref "D2") (pin "C") (pinfunction "C_C") (pintype "passive"))
      (node (ref "D3") (pin "C") (pinfunction "C_C") (pintype "passive"))
      (node (ref "D4") (pin "C") (pinfunction "C_C") (pintype "passive"))
      (node (ref "D5") (pin "C") (pinfunction "C_C") (pintype "passive"))
      (node (ref "D6") (pin "C") (pinfunction "C_C") (pintype "passive"))
      (node (ref "D7") (pin "C") (pinfunction "C_C") (pintype "passive"))
      (node (ref "D8") (pin "C") (pinfunction "C_C") (pintype "passive"))
      (node (ref "Q2") (pin "3") (pinfunction "D_3") (pintype "passive"))
    )
    (net (code "23") (name "Net-(Q3-D)") (class "Default")
      (node (ref "DI1") (pin "P$3") (pinfunction "A_P$3") (pintype "passive"))
      (node (ref "DI1") (pin "P$8") (pinfunction "A_P$8") (pintype "passive"))
      (node (ref "Q3") (pin "3") (pinfunction "D_3") (pintype "passive"))
    )
    (net (code "24") (name "Net-(Q4-D)") (class "Default")
      (node (ref "DI2") (pin "P$3") (pinfunction "A_P$3") (pintype "passive"))
      (node (ref "DI2") (pin "P$8") (pinfunction "A_P$8") (pintype "passive"))
      (node (ref "Q4") (pin "3") (pinfunction "D_3") (pintype "passive"))
    )
    (net (code "25") (name "Net-(Q5-D)") (class "Default")
      (node (ref "DI3") (pin "P$3") (pinfunction "A_P$3") (pintype "passive"))
      (node (ref "DI3") (pin "P$8") (pinfunction "A_P$8") (pintype "passive"))
      (node (ref "Q5") (pin "3") (pinfunction "D_3") (pintype "passive"))
    )
    (net (code "26") (name "Net-(U$2-RINGX)") (class "Default")
      (node (ref "C12") (pin "2") (pinfunction "2_2") (pintype "passive"))
      (node (ref "C13") (pin "1") (pinfunction "1_1") (pintype "passive"))
      (node (ref "R43") (pin "2") (pinfunction "2_2") (pintype "passive"))
      (node (ref "U$2") (pin "P2") (pinfunction "RINGX_P2") (pintype "bidirectional"))
      (node (ref "U$2") (pin "P3") (pinfunction "TIPX_P3") (pintype "bidirectional"))
      (node (ref "U$2") (pin "P4") (pinfunction "TIP_P4") (pintype "bidirectional"))
    )
    (net (code "27") (name "Net-(U1-PB1(OC1A))") (class "Default")
      (node (ref "R41") (pin "1") (pinfunction "1_1") (pintype "passive"))
      (node (ref "U1") (pin "13") (pinfunction "PB1(OC1A)_13") (pintype "bidirectional"))
    )
    (net (code "28") (name "Net-(U1-PB2(SS{slash}OC1B))") (class "Default")
      (node (ref "R42") (pin "1") (pinfunction "1_1") (pintype "passive"))
      (node (ref "U1") (pin "14") (pinfunction "PB2(SS/OC1B)_14") (pintype "bidirectional"))
    )
    (net (code "29") (name "Net-(U1-PB6(XTAL1{slash}TOSC1))") (class "Default")
      (node (ref "C3") (pin "2") (pinfunction "2_2") (pintype "passive"))
      (node (ref "U1") (pin "7") (pinfunction "PB6(XTAL1/TOSC1)_7") (pintype "bidirectional"))
      (node (ref "XTAL1") (pin "P2") (pinfunction "2_P2") (pintype "passive"))
    )
    (net (code "30") (name "Net-(U1-PB7(XTAL2{slash}TOSC2))") (class "Default")
      (node (ref "C4") (pin "2") (pinfunction "2_2") (pintype "passive"))
      (node (ref "U1") (pin "8") (pinfunction "PB7(XTAL2/TOSC2)_8") (pintype "bidirectional"))
      (node (ref "XTAL1") (pin "P1") (pinfunction "1_P1") (pintype "passive"))
    )
    (net (code "31") (name "Net-(U2-RA0)") (class "Default")
      (node (ref "R19") (pin "2") (pinfunction "2_2") (pintype "passive"))
      (node (ref "U2") (pin "19") (pinfunction "RA0_19") (pintype "bidirectional"))
    )
    (net (code "32") (name "Net-(U2-RA1)") (class "Default")
      (node (ref "R20") (pin "2") (pinfunction "2_2") (pintype "passive"))
      (node (ref "U2") (pin "20") (pinfunction "RA1_20") (pintype "bidirectional"))
    )
    (net (code "33") (name "Net-(U2-RA2)") (class "Default")
      (node (ref "R21") (pin "2") (pinfunction "2_2") (pintype "passive"))
      (node (ref "U2") (pin "21") (pinfunction "RA2_21") (pintype "bidirectional"))
    )
    (net (code "34") (name "Net-(U2-RA3)") (class "Default")
      (node (ref "R22") (pin "2") (pinfunction "2_2") (pintype "passive"))
      (node (ref "U2") (pin "22") (pinfunction "RA3_22") (pintype "bidirectional"))
    )
    (net (code "35") (name "Net-(U2-RA5)") (class "Default")
      (node (ref "R23") (pin "2") (pinfunction "2_2") (pintype "passive"))
      (node (ref "U2") (pin "24") (pinfunction "RA5_24") (pintype "bidirectional"))
    )
    (net (code "36") (name "Net-(U2-RB0)") (class "Default")
      (node (ref "R13") (pin "2") (pinfunction "2_2") (pintype "passive"))
      (node (ref "U2") (pin "8") (pinfunction "RB0_8") (pintype "bidirectional"))
    )
    (net (code "37") (name "Net-(U2-RB1)") (class "Default")
      (node (ref "R14") (pin "2") (pinfunction "2_2") (pintype "passive"))
      (node (ref "U2") (pin "9") (pinfunction "RB1_9") (pintype "bidirectional"))
    )
    (net (code "38") (name "Net-(U2-RB2)") (class "Default")
      (node (ref "R15") (pin "2") (pinfunction "2_2") (pintype "passive"))
      (node (ref "U2") (pin "10") (pinfunction "RB2_10") (pintype "bidirectional"))
    )
    (net (code "39") (name "Net-(U2-RB3)") (class "Default")
      (node (ref "R16") (pin "2") (pinfunction "2_2") (pintype "passive"))
      (node (ref "U2") (pin "11") (pinfunction "RB3_11") (pintype "bidirectional"))
    )
    (net (code "40") (name "Net-(U2-RB4)") (class "Default")
      (node (ref "R17") (pin "2") (pinfunction "2_2") (pintype "passive"))
      (node (ref "U2") (pin "14") (pinfunction "RB4_14") (pintype "bidirectional"))
    )
    (net (code "41") (name "Net-(U2-RB5)") (class "Default")
      (node (ref "R18") (pin "2") (pinfunction "2_2") (pintype "passive"))
      (node (ref "U2") (pin "15") (pinfunction "RB5_15") (pintype "bidirectional"))
    )
    (net (code "42") (name "Net-(U2-RC2)") (class "Default")
      (node (ref "R1") (pin "2") (pinfunction "2_2") (pintype "passive"))
      (node (ref "U2") (pin "36") (pinfunction "RC2_36") (pintype "bidirectional"))
    )
    (net (code "43") (name "Net-(U2-RC3)") (class "Default")
      (node (ref "R2") (pin "2") (pinfunction "2_2") (pintype "passive"))
      (node (ref "U2") (pin "37") (pinfunction "RC3_37") (pintype "bidirectional"))
    )
    (net (code "44") (name "Net-(U2-RC4)") (class "Default")
      (node (ref "R7") (pin "2") (pinfunction "2_2") (pintype "passive"))
      (node (ref "U2") (pin "42") (pinfunction "RC4_42") (pintype "bidirectional"))
    )
    (net (code "45") (name "Net-(U2-RC5)") (class "Default")
      (node (ref "R8") (pin "2") (pinfunction "2_2") (pintype "passive"))
      (node (ref "U2") (pin "43") (pinfunction "RC5_43") (pintype "bidirectional"))
    )
    (net (code "46") (name "Net-(U2-RC6)") (class "Default")
      (node (ref "R9") (pin "2") (pinfunction "2_2") (pintype "passive"))
      (node (ref "U2") (pin "44") (pinfunction "RC6_44") (pintype "bidirectional"))
    )
    (net (code "47") (name "Net-(U2-RC7)") (class "Default")
      (node (ref "R10") (pin "2") (pinfunction "2_2") (pintype "passive"))
      (node (ref "U2") (pin "1") (pinfunction "RC7_1") (pintype "bidirectional"))
    )
    (net (code "48") (name "Net-(U2-RD0)") (class "Default")
      (node (ref "R3") (pin "2") (pinfunction "2_2") (pintype "passive"))
      (node (ref "U2") (pin "38") (pinfunction "RD0_38") (pintype "bidirectional"))
    )
    (net (code "49") (name "Net-(U2-RD1)") (class "Default")
      (node (ref "R4") (pin "2") (pinfunction "2_2") (pintype "passive"))
      (node (ref "U2") (pin "39") (pinfunction "RD1_39") (pintype "bidirectional"))
    )
    (net (code "50") (name "Net-(U2-RD2)") (class "Default")
      (node (ref "R5") (pin "2") (pinfunction "2_2") (pintype "passive"))
      (node (ref "U2") (pin "40") (pinfunction "RD2_40") (pintype "bidirectional"))
    )
    (net (code "51") (name "Net-(U2-RD3)") (class "Default")
      (node (ref "R6") (pin "2") (pinfunction "2_2") (pintype "passive"))
      (node (ref "U2") (pin "41") (pinfunction "RD3_41") (pintype "bidirectional"))
    )
    (net (code "52") (name "Net-(U2-RD4)") (class "Default")
      (node (ref "R11") (pin "2") (pinfunction "2_2") (pintype "passive"))
      (node (ref "U2") (pin "2") (pinfunction "RD4_2") (pintype "bidirectional"))
    )
    (net (code "53") (name "Net-(U2-RD5)") (class "Default")
      (node (ref "R12") (pin "2") (pinfunction "2_2") (pintype "passive"))
      (node (ref "U2") (pin "3") (pinfunction "RD5_3") (pintype "bidirectional"))
    )
    (net (code "54") (name "Net-(U2-RE0)") (class "Default")
      (node (ref "R24") (pin "2") (pinfunction "2_2") (pintype "passive"))
      (node (ref "U2") (pin "25") (pinfunction "RE0_25") (pintype "bidirectional"))
    )
    (net (code "55") (name "PAD1") (class "Default")
      (node (ref "P1") (pin "P$1") (pinfunction "P1_P$1") (pintype "bidirectional"))
      (node (ref "R1") (pin "1") (pinfunction "1_1") (pintype "passive"))
    )
    (net (code "56") (name "PAD2") (class "Default")
      (node (ref "P2") (pin "P$1") (pinfunction "P1_P$1") (pintype "bidirectional"))
      (node (ref "R2") (pin "1") (pinfunction "1_1") (pintype "passive"))
    )
    (net (code "57") (name "PAD3") (class "Default")
      (node (ref "P3") (pin "P$1") (pinfunction "P1_P$1") (pintype "bidirectional"))
      (node (ref "R3") (pin "1") (pinfunction "1_1") (pintype "passive"))
    )
    (net (code "58") (name "PAD4") (class "Default")
      (node (ref "P4") (pin "P$1") (pinfunction "P1_P$1") (pintype "bidirectional"))
      (node (ref "R4") (pin "1") (pinfunction "1_1") (pintype "passive"))
    )
    (net (code "59") (name "PAD5") (class "Default")
      (node (ref "P5") (pin "P$1") (pinfunction "P1_P$1") (pintype "bidirectional"))
      (node (ref "R5") (pin "1") (pinfunction "1_1") (pintype "passive"))
    )
    (net (code "60") (name "PAD6") (class "Default")
      (node (ref "P6") (pin "P$1") (pinfunction "P1_P$1") (pintype "bidirectional"))
      (node (ref "R6") (pin "1") (pinfunction "1_1") (pintype "passive"))
    )
    (net (code "61") (name "PAD7") (class "Default")
      (node (ref "P7") (pin "P$1") (pinfunction "P1_P$1") (pintype "bidirectional"))
      (node (ref "R7") (pin "1") (pinfunction "1_1") (pintype "passive"))
    )
    (net (code "62") (name "PAD8") (class "Default")
      (node (ref "P8") (pin "P$1") (pinfunction "P1_P$1") (pintype "bidirectional"))
      (node (ref "R8") (pin "1") (pinfunction "1_1") (pintype "passive"))
    )
    (net (code "63") (name "PAD9") (class "Default")
      (node (ref "P9") (pin "P$1") (pinfunction "P1_P$1") (pintype "bidirectional"))
      (node (ref "R9") (pin "1") (pinfunction "1_1") (pintype "passive"))
    )
    (net (code "64") (name "PAD10") (class "Default")
      (node (ref "P10") (pin "P$1") (pinfunction "P1_P$1") (pintype "bidirectional"))
      (node (ref "R10") (pin "1") (pinfunction "1_1") (pintype "passive"))
    )
    (net (code "65") (name "PAD11") (class "Default")
      (node (ref "P11") (pin "P$1") (pinfunction "P1_P$1") (pintype "bidirectional"))
      (node (ref "R11") (pin "1") (pinfunction "1_1") (pintype "passive"))
    )
    (net (code "66") (name "PAD12") (class "Default")
      (node (ref "P12") (pin "P$1") (pinfunction "P1_P$1") (pintype "bidirectional"))
      (node (ref "R12") (pin "1") (pinfunction "1_1") (pintype "passive"))
    )
    (net (code "67") (name "PAD13") (class "Default")
      (node (ref "P13") (pin "P$1") (pinfunction "P1_P$1") (pintype "bidirectional"))
      (node (ref "R13") (pin "1") (pinfunction "1_1") (pintype "passive"))
    )
    (net (code "68") (name "PAD14") (class "Default")
      (node (ref "P14") (pin "P$1") (pinfunction "P1_P$1") (pintype "bidirectional"))
      (node (ref "R14") (pin "1") (pinfunction "1_1") (pintype "passive"))
    )
    (net (code "69") (name "PAD15") (class "Default")
      (node (ref "P15") (pin "P$1") (pinfunction "P1_P$1") (pintype "bidirectional"))
      (node (ref "R15") (pin "1") (pinfunction "1_1") (pintype "passive"))
    )
    (net (code "70") (name "PAD16") (class "Default")
      (node (ref "P16") (pin "P$1") (pinfunction "P1_P$1") (pintype "bidirectional"))
      (node (ref "R16") (pin "1") (pinfunction "1_1") (pintype "passive"))
    )
    (net (code "71") (name "PAD17") (class "Default")
      (node (ref "P17") (pin "P$1") (pinfunction "P1_P$1") (pintype "bidirectional"))
      (node (ref "R17") (pin "1") (pinfunction "1_1") (pintype "passive"))
    )
    (net (code "72") (name "PAD18") (class "Default")
      (node (ref "P18") (pin "P$1") (pinfunction "P1_P$1") (pintype "bidirectional"))
      (node (ref "R18") (pin "1") (pinfunction "1_1") (pintype "passive"))
    )
    (net (code "73") (name "PAD19") (class "Default")
      (node (ref "P19") (pin "P$1") (pinfunction "P1_P$1") (pintype "bidirectional"))
      (node (ref "R19") (pin "1") (pinfunction "1_1") (pintype "passive"))
    )
    (net (code "74") (name "PAD20") (class "Default")
      (node (ref "P20") (pin "P$1") (pinfunction "P1_P$1") (pintype "bidirectional"))
      (node (ref "R20") (pin "1") (pinfunction "1_1") (pintype "passive"))
    )
    (net (code "75") (name "PAD21") (class "Default")
      (node (ref "P21") (pin "P$1") (pinfunction "P1_P$1") (pintype "bidirectional"))
      (node (ref "R21") (pin "1") (pinfunction "1_1") (pintype "passive"))
    )
    (net (code "76") (name "PAD22") (class "Default")
      (node (ref "P22") (pin "P$1") (pinfunction "P1_P$1") (pintype "bidirectional"))
      (node (ref "R22") (pin "1") (pinfunction "1_1") (pintype "passive"))
    )
    (net (code "77") (name "PAD23") (class "Default")
      (node (ref "P23") (pin "P$1") (pinfunction "P1_P$1") (pintype "bidirectional"))
      (node (ref "R23") (pin "1") (pinfunction "1_1") (pintype "passive"))
    )
    (net (code "78") (name "PAD24") (class "Default")
      (node (ref "P24") (pin "P$1") (pinfunction "P1_P$1") (pintype "bidirectional"))
      (node (ref "R24") (pin "1") (pinfunction "1_1") (pintype "passive"))
    )
    (net (code "79") (name "QUAD1") (class "Default")
      (node (ref "ENC1") (pin "A") (pinfunction "A_A") (pintype "passive"))
      (node (ref "R37") (pin "1") (pinfunction "1_1") (pintype "passive"))
      (node (ref "U2") (pin "35") (pinfunction "RC1_35") (pintype "bidirectional"))
    )
    (net (code "80") (name "QUAD2") (class "Default")
      (node (ref "ENC1") (pin "B") (pinfunction "B_B") (pintype "passive"))
      (node (ref "R36") (pin "1") (pinfunction "1_1") (pintype "passive"))
      (node (ref "U2") (pin "32") (pinfunction "RC0_32") (pintype "bidirectional"))
    )
    (net (code "81") (name "SCLK") (class "Default")
      (node (ref "IC1") (pin "11") (pinfunction "SCLK_11") (pintype "input"))
      (node (ref "IC2") (pin "11") (pinfunction "SCLK_11") (pintype "input"))
      (node (ref "J1") (pin "5") (pinfunction "PGC_5") (pintype "passive"))
      (node (ref "U2") (pin "16") (pinfunction "RB6_16") (pintype "bidirectional"))
    )
    (net (code "82") (name "SD-CK") (class "Default")
      (node (ref "CN1") (pin "5") (pinfunction "P$5_5") (pintype "bidirectional"))
      (node (ref "J3") (pin "3") (pinfunction "SCK_3") (pintype "passive"))
      (node (ref "U1") (pin "17") (pinfunction "PB5(SCK)_17") (pintype "bidirectional"))
    )
    (net (code "83") (name "SD-CS") (class "Default")
      (node (ref "CN1") (pin "2") (pinfunction "P$2_2") (pintype "bidirectional"))
      (node (ref "U1") (pin "23") (pinfunction "PC0(ADC0)_23") (pintype "bidirectional"))
    )
    (net (code "84") (name "SD-DI") (class "Default")
      (node (ref "CN1") (pin "3") (pinfunction "P$3_3") (pintype "bidirectional"))
      (node (ref "J3") (pin "4") (pinfunction "MOSI_4") (pintype "passive"))
      (node (ref "U1") (pin "15") (pinfunction "PB3(MOSI/OC2)_15") (pintype "bidirectional"))
    )
    (net (code "85") (name "SD-DO") (class "Default")
      (node (ref "CN1") (pin "7") (pinfunction "P$7_7") (pintype "bidirectional"))
      (node (ref "J3") (pin "1") (pinfunction "MISO_1") (pintype "passive"))
      (node (ref "U1") (pin "16") (pinfunction "PB4(MISO)_16") (pintype "bidirectional"))
    )
    (net (code "86") (name "SDA") (class "Default")
      (node (ref "IC1") (pin "14") (pinfunction "SDA_14") (pintype "input"))
      (node (ref "J1") (pin "4") (pinfunction "PGD_4") (pintype "passive"))
      (node (ref "U2") (pin "17") (pinfunction "RB7_17") (pintype "bidirectional"))
    )
    (net (code "87") (name "SEGA") (class "Default")
      (node (ref "IC1") (pin "6") (pinfunction "Q6_6") (pintype "output"))
      (node (ref "R25") (pin "1") (pinfunction "1_1") (pintype "passive"))
    )
    (net (code "88") (name "SEGB") (class "Default")
      (node (ref "IC1") (pin "4") (pinfunction "Q4_4") (pintype "output"))
      (node (ref "R26") (pin "1") (pinfunction "1_1") (pintype "passive"))
    )
    (net (code "89") (name "SEGC") (class "Default")
      (node (ref "IC1") (pin "2") (pinfunction "Q2_2") (pintype "output"))
      (node (ref "R27") (pin "1") (pinfunction "1_1") (pintype "passive"))
    )
    (net (code "90") (name "SEGD") (class "Default")
      (node (ref "IC1") (pin "1") (pinfunction "Q1_1") (pintype "output"))
      (node (ref "R28") (pin "1") (pinfunction "1_1") (pintype "passive"))
    )
    (net (code "91") (name "SEGE") (class "Default")
      (node (ref "IC1") (pin "5") (pinfunction "Q5_5") (pintype "output"))
      (node (ref "R29") (pin "1") (pinfunction "1_1") (pintype "passive"))
    )
    (net (code "92") (name "SEGF") (class "Default")
      (node (ref "IC1") (pin "7") (pinfunction "Q7_7") (pintype "output"))
      (node (ref "R30") (pin "1") (pinfunction "1_1") (pintype "passive"))
    )
    (net (code "93") (name "SEGG") (class "Default")
      (node (ref "IC1") (pin "15") (pinfunction "Q0_15") (pintype "output"))
      (node (ref "R31") (pin "1") (pinfunction "1_1") (pintype "passive"))
    )
    (net (code "94") (name "SEGP") (class "Default")
      (node (ref "IC1") (pin "3") (pinfunction "Q3_3") (pintype "output"))
      (node (ref "R32") (pin "1") (pinfunction "1_1") (pintype "passive"))
    )
    (net (code "95") (name "SEG_A") (class "Default")
      (node (ref "D10") (pin "A") (pinfunction "A_A") (pintype "passive"))
      (node (ref "D2") (pin "A") (pinfunction "A_A") (pintype "passive"))
      (node (ref "DI1") (pin "P$10") (pinfunction "A_P$10") (pintype "passive"))
      (node (ref "DI2") (pin "P$10") (pinfunction "A_P$10") (pintype "passive"))
      (node (ref "DI3") (pin "P$10") (pinfunction "A_P$10") (pintype "passive"))
      (node (ref "R25") (pin "2") (pinfunction "2_2") (pintype "passive"))
      (node (ref "SW10") (pin "1B") (pinfunction "1B_1B") (pintype "passive"))
      (node (ref "SW15") (pin "1B") (pinfunction "1B_1B") (pintype "passive"))
      (node (ref "SW5") (pin "1B") (pinfunction "1B_1B") (pintype "passive"))
    )
    (net (code "96") (name "SEG_B") (class "Default")
      (node (ref "D13") (pin "A") (pinfunction "A_A") (pintype "passive"))
      (node (ref "D5") (pin "A") (pinfunction "A_A") (pintype "passive"))
      (node (ref "DI1") (pin "P$9") (pinfunction "B_P$9") (pintype "passive"))
      (node (ref "DI2") (pin "P$9") (pinfunction "B_P$9") (pintype "passive"))
      (node (ref "DI3") (pin "P$9") (pinfunction "B_P$9") (pintype "passive"))
      (node (ref "R26") (pin "2") (pinfunction "2_2") (pintype "passive"))
    )
    (net (code "97") (name "SEG_C") (class "Default")
      (node (ref "D8") (pin "A") (pinfunction "A_A") (pintype "passive"))
      (node (ref "DI1") (pin "P$7") (pinfunction "C_P$7") (pintype "passive"))
      (node (ref "DI2") (pin "P$7") (pinfunction "C_P$7") (pintype "passive"))
      (node (ref "DI3") (pin "P$7") (pinfunction "C_P$7") (pintype "passive"))
      (node (ref "R27") (pin "2") (pinfunction "2_2") (pintype "passive"))
      (node (ref "SW13") (pin "1B") (pinfunction "1B_1B") (pintype "passive"))
      (node (ref "SW3") (pin "1B") (pinfunction "1B_1B") (pintype "passive"))
      (node (ref "SW8") (pin "1B") (pinfunction "1B_1B") (pintype "passive"))
    )
    (net (code "98") (name "SEG_D") (class "Default")
      (node (ref "D14") (pin "A") (pinfunction "A_A") (pintype "passive"))
      (node (ref "D6") (pin "A") (pinfunction "A_A") (pintype "passive"))
      (node (ref "DI1") (pin "P$5") (pinfunction "D_P$5") (pintype "passive"))
      (node (ref "DI2") (pin "P$5") (pinfunction "D_P$5") (pintype "passive"))
      (node (ref "DI3") (pin "P$5") (pinfunction "D_P$5") (pintype "passive"))
      (node (ref "R28") (pin "2") (pinfunction "2_2") (pintype "passive"))
      (node (ref "SW14") (pin "1B") (pinfunction "1B_1B") (pintype "passive"))
      (node (ref "SW4") (pin "1B") (pinfunction "1B_1B") (pintype "passive"))
      (node (ref "SW9") (pin "1B") (pinfunction "1B_1B") (pintype "passive"))
    )
    (net (code "99") (name "SEG_E") (class "Default")
      (node (ref "D11") (pin "A") (pinfunction "A_A") (pintype "passive"))
      (node (ref "D3") (pin "A") (pinfunction "A_A") (pintype "passive"))
      (node (ref "DI1") (pin "P$2") (pinfunction "E_P$2") (pintype "passive"))
      (node (ref "DI2") (pin "P$2") (pinfunction "E_P$2") (pintype "passive"))
      (node (ref "DI3") (pin "P$2") (pinfunction "E_P$2") (pintype "passive"))
      (node (ref "R29") (pin "2") (pinfunction "2_2") (pintype "passive"))
      (node (ref "SW1") (pin "1B") (pinfunction "1B_1B") (pintype "passive"))
      (node (ref "SW11") (pin "1B") (pinfunction "1B_1B") (pintype "passive"))
      (node (ref "SW6") (pin "1B") (pinfunction "1B_1B") (pintype "passive"))
    )
    (net (code "100") (name "SEG_F") (class "Default")
      (node (ref "D1") (pin "A") (pinfunction "A_A") (pintype "passive"))
      (node (ref "D9") (pin "A") (pinfunction "A_A") (pintype "passive"))
      (node (ref "DI1") (pin "P$1") (pinfunction "F_P$1") (pintype "passive"))
      (node (ref "DI2") (pin "P$1") (pinfunction "F_P$1") (pintype "passive"))
      (node (ref "DI3") (pin "P$1") (pinfunction "F_P$1") (pintype "passive"))
      (node (ref "R30") (pin "2") (pinfunction "2_2") (pintype "passive"))
    )
    (net (code "101") (name "SEG_G") (class "Default")
      (node (ref "D15") (pin "A") (pinfunction "A_A") (pintype "passive"))
      (node (ref "D7") (pin "A") (pinfunction "A_A") (pintype "passive"))
      (node (ref "DI1") (pin "P$6") (pinfunction "G_P$6") (pintype "passive"))
      (node (ref "DI2") (pin "P$6") (pinfunction "G_P$6") (pintype "passive"))
      (node (ref "DI3") (pin "P$6") (pinfunction "G_P$6") (pintype "passive"))
      (node (ref "ENC1") (pin "E") (pinfunction "2_E") (pintype "passive"))
      (node (ref "R31") (pin "2") (pinfunction "2_2") (pintype "passive"))
    )
    (net (code "102") (name "SEG_P") (class "Default")
      (node (ref "D12") (pin "A") (pinfunction "A_A") (pintype "passive"))
      (node (ref "D4") (pin "A") (pinfunction "A_A") (pintype "passive"))
      (node (ref "DI1") (pin "P$4") (pinfunction "DP_P$4") (pintype "passive"))
      (node (ref "DI2") (pin "P$4") (pinfunction "DP_P$4") (pintype "passive"))
      (node (ref "DI3") (pin "P$4") (pinfunction "DP_P$4") (pintype "passive"))
      (node (ref "R32") (pin "2") (pinfunction "2_2") (pintype "passive"))
      (node (ref "SW12") (pin "1B") (pinfunction "1B_1B") (pintype "passive"))
      (node (ref "SW2") (pin "1B") (pinfunction "1B_1B") (pintype "passive"))
      (node (ref "SW7") (pin "1B") (pinfunction "1B_1B") (pintype "passive"))
    )
    (net (code "103") (name "SPARE5") (class "Default")
      (node (ref "U2") (pin "23") (pinfunction "RA4_23") (pintype "bidirectional"))
    )
    (net (code "104") (name "TOUCH-RX") (class "Default")
      (node (ref "U1") (pin "31") (pinfunction "PD1(TXD)_31") (pintype "bidirectional"))
      (node (ref "U2") (pin "5") (pinfunction "RD7_5") (pintype "bidirectional"))
    )
    (net (code "105") (name "TOUCH-TX") (class "Default")
      (node (ref "U1") (pin "30") (pinfunction "PD0(RXD)_30") (pintype "bidirectional"))
      (node (ref "U2") (pin "4") (pinfunction "RD6_4") (pintype "bidirectional"))
    )
    (net (code "106") (name "VCC-CPU") (class "Default")
      (node (ref "C15") (pin "+") (pinfunction "+_+") (pintype "passive"))
      (node (ref "C5") (pin "1") (pinfunction "1_1") (pintype "passive"))
      (node (ref "C7") (pin "1") (pinfunction "1_1") (pintype "passive"))
      (node (ref "J3") (pin "2") (pinfunction "+V_2") (pintype "passive"))
      (node (ref "L3") (pin "2") (pinfunction "2_2") (pintype "passive"))
      (node (ref "R44") (pin "2") (pinfunction "2_2") (pintype "passive"))
      (node (ref "U1") (pin "18") (pinfunction "AVCC_18") (pintype "bidirectional"))
      (node (ref "U1") (pin "4") (pinfunction "VCC_4") (pintype "bidirectional"))
      (node (ref "U1") (pin "6") (pinfunction "VCC_6") (pintype "bidirectional"))
    )
    (net (code "107") (name "VCC-TOUCH") (class "Default")
      (node (ref "C1") (pin "1") (pinfunction "1_1") (pintype "passive"))
      (node (ref "C16") (pin "+") (pinfunction "+_+") (pintype "passive"))
      (node (ref "C2") (pin "1") (pinfunction "1_1") (pintype "passive"))
      (node (ref "J1") (pin "2") (pinfunction "+V_2") (pintype "passive"))
      (node (ref "L1") (pin "2") (pinfunction "2_2") (pintype "passive"))
      (node (ref "R33") (pin "1") (pinfunction "1_1") (pintype "passive"))
      (node (ref "R36") (pin "2") (pinfunction "2_2") (pintype "passive"))
      (node (ref "R37") (pin "2") (pinfunction "2_2") (pintype "passive"))
      (node (ref "R38") (pin "1") (pinfunction "1_1") (pintype "passive"))
      (node (ref "R39") (pin "1") (pinfunction "1_1") (pintype "passive"))
      (node (ref "R40") (pin "2") (pinfunction "2_2") (pintype "passive"))
      (node (ref "U2") (pin "28") (pinfunction "VDD_28") (pintype "power_in"))
      (node (ref "U2") (pin "7") (pinfunction "VDD_2_7") (pintype "power_in"))
    )
    (net (code "108") (name "VCC-UI") (class "Default")
      (node (ref "C10") (pin "1") (pinfunction "1_1") (pintype "passive"))
      (node (ref "C11") (pin "1") (pinfunction "1_1") (pintype "passive"))
      (node (ref "C17") (pin "+") (pinfunction "+_+") (pintype "passive"))
      (node (ref "IC1") (pin "10") (pinfunction "~{RST}_10") (pintype "input"))
      (node (ref "IC1") (pin "16") (pinfunction "V+_16") (pintype "power_in"))
      (node (ref "IC2") (pin "10") (pinfunction "~{RST}_10") (pintype "input"))
      (node (ref "IC2") (pin "16") (pinfunction "V+_16") (pintype "power_in"))
      (node (ref "L2") (pin "1") (pinfunction "1_1") (pintype "passive"))
    )
    (net (code "109") (name "unconnected-(CN1-P$1-Pad1)") (class "Default")
      (node (ref "CN1") (pin "1") (pinfunction "P$1_1") (pintype "bidirectional"))
    )
    (net (code "110") (name "unconnected-(CN1-P$8-Pad8)") (class "Default")
      (node (ref "CN1") (pin "8") (pinfunction "P$8_8") (pintype "bidirectional"))
    )
    (net (code "111") (name "unconnected-(CN1-P$9-Pad9)") (class "Default")
      (node (ref "CN1") (pin "9") (pinfunction "P$9_9") (pintype "bidirectional"))
    )
    (net (code "112") (name "unconnected-(IC2A-Q7S-Pad9)") (class "Default")
      (node (ref "IC2") (pin "9") (pinfunction "Q7S_9") (pintype "output"))
    )
    (net (code "113") (name "unconnected-(SW1-Pad1A)") (class "Default")
      (node (ref "SW1") (pin "1A") (pinfunction "1A_1A") (pintype "passive"))
    )
    (net (code "114") (name "unconnected-(SW1-Pad2A)") (class "Default")
      (node (ref "SW1") (pin "2A") (pinfunction "2A_2A") (pintype "passive"))
    )
    (net (code "115") (name "unconnected-(SW2-Pad1A)") (class "Default")
      (node (ref "SW2") (pin "1A") (pinfunction "1A_1A") (pintype "passive"))
    )
    (net (code "116") (name "unconnected-(SW2-Pad2A)") (class "Default")
      (node (ref "SW2") (pin "2A") (pinfunction "2A_2A") (pintype "passive"))
    )
    (net (code "117") (name "unconnected-(SW3-Pad1A)") (class "Default")
      (node (ref "SW3") (pin "1A") (pinfunction "1A_1A") (pintype "passive"))
    )
    (net (code "118") (name "unconnected-(SW3-Pad2A)") (class "Default")
      (node (ref "SW3") (pin "2A") (pinfunction "2A_2A") (pintype "passive"))
    )
    (net (code "119") (name "unconnected-(SW4-Pad1A)") (class "Default")
      (node (ref "SW4") (pin "1A") (pinfunction "1A_1A") (pintype "passive"))
    )
    (net (code "120") (name "unconnected-(SW4-Pad2A)") (class "Default")
      (node (ref "SW4") (pin "2A") (pinfunction "2A_2A") (pintype "passive"))
    )
    (net (code "121") (name "unconnected-(SW5-Pad1A)") (class "Default")
      (node (ref "SW5") (pin "1A") (pinfunction "1A_1A") (pintype "passive"))
    )
    (net (code "122") (name "unconnected-(SW5-Pad2A)") (class "Default")
      (node (ref "SW5") (pin "2A") (pinfunction "2A_2A") (pintype "passive"))
    )
    (net (code "123") (name "unconnected-(SW6-Pad1A)") (class "Default")
      (node (ref "SW6") (pin "1A") (pinfunction "1A_1A") (pintype "passive"))
    )
    (net (code "124") (name "unconnected-(SW6-Pad2A)") (class "Default")
      (node (ref "SW6") (pin "2A") (pinfunction "2A_2A") (pintype "passive"))
    )
    (net (code "125") (name "unconnected-(SW7-Pad1A)") (class "Default")
      (node (ref "SW7") (pin "1A") (pinfunction "1A_1A") (pintype "passive"))
    )
    (net (code "126") (name "unconnected-(SW7-Pad2A)") (class "Default")
      (node (ref "SW7") (pin "2A") (pinfunction "2A_2A") (pintype "passive"))
    )
    (net (code "127") (name "unconnected-(SW8-Pad1A)") (class "Default")
      (node (ref "SW8") (pin "1A") (pinfunction "1A_1A") (pintype "passive"))
    )
    (net (code "128") (name "unconnected-(SW8-Pad2A)") (class "Default")
      (node (ref "SW8") (pin "2A") (pinfunction "2A_2A") (pintype "passive"))
    )
    (net (code "129") (name "unconnected-(SW9-Pad1A)") (class "Default")
      (node (ref "SW9") (pin "1A") (pinfunction "1A_1A") (pintype "passive"))
    )
    (net (code "130") (name "unconnected-(SW9-Pad2A)") (class "Default")
      (node (ref "SW9") (pin "2A") (pinfunction "2A_2A") (pintype "passive"))
    )
    (net (code "131") (name "unconnected-(SW10-Pad1A)") (class "Default")
      (node (ref "SW10") (pin "1A") (pinfunction "1A_1A") (pintype "passive"))
    )
    (net (code "132") (name "unconnected-(SW10-Pad2A)") (class "Default")
      (node (ref "SW10") (pin "2A") (pinfunction "2A_2A") (pintype "passive"))
    )
    (net (code "133") (name "unconnected-(SW11-Pad1A)") (class "Default")
      (node (ref "SW11") (pin "1A") (pinfunction "1A_1A") (pintype "passive"))
    )
    (net (code "134") (name "unconnected-(SW11-Pad2A)") (class "Default")
      (node (ref "SW11") (pin "2A") (pinfunction "2A_2A") (pintype "passive"))
    )
    (net (code "135") (name "unconnected-(SW12-Pad1A)") (class "Default")
      (node (ref "SW12") (pin "1A") (pinfunction "1A_1A") (pintype "passive"))
    )
    (net (code "136") (name "unconnected-(SW12-Pad2A)") (class "Default")
      (node (ref "SW12") (pin "2A") (pinfunction "2A_2A") (pintype "passive"))
    )
    (net (code "137") (name "unconnected-(SW13-Pad1A)") (class "Default")
      (node (ref "SW13") (pin "1A") (pinfunction "1A_1A") (pintype "passive"))
    )
    (net (code "138") (name "unconnected-(SW13-Pad2A)") (class "Default")
      (node (ref "SW13") (pin "2A") (pinfunction "2A_2A") (pintype "passive"))
    )
    (net (code "139") (name "unconnected-(SW14-Pad1A)") (class "Default")
      (node (ref "SW14") (pin "1A") (pinfunction "1A_1A") (pintype "passive"))
    )
    (net (code "140") (name "unconnected-(SW14-Pad2A)") (class "Default")
      (node (ref "SW14") (pin "2A") (pinfunction "2A_2A") (pintype "passive"))
    )
    (net (code "141") (name "unconnected-(SW15-Pad1A)") (class "Default")
      (node (ref "SW15") (pin "1A") (pinfunction "1A_1A") (pintype "passive"))
    )
    (net (code "142") (name "unconnected-(SW15-Pad2A)") (class "Default")
      (node (ref "SW15") (pin "2A") (pinfunction "2A_2A") (pintype "passive"))
    )
    (net (code "143") (name "unconnected-(SW16-PadNC)") (class "Default")
      (node (ref "SW16") (pin "NC") (pinfunction "NC_NC") (pintype "bidirectional"))
    )
    (net (code "144") (name "unconnected-(U$2-SPARE-PadP6)") (class "Default")
      (node (ref "U$2") (pin "P6") (pinfunction "SPARE_P6") (pintype "bidirectional"))
    )
    (net (code "145") (name "unconnected-(U1-ADC6-Pad19)") (class "Default")
      (node (ref "U1") (pin "19") (pinfunction "ADC6_19") (pintype "bidirectional"))
    )
    (net (code "146") (name "unconnected-(U1-ADC7-Pad22)") (class "Default")
      (node (ref "U1") (pin "22") (pinfunction "ADC7_22") (pintype "bidirectional"))
    )
    (net (code "147") (name "unconnected-(U1-AREF-Pad20)") (class "Default")
      (node (ref "U1") (pin "20") (pinfunction "AREF_20") (pintype "bidirectional"))
    )
    (net (code "148") (name "unconnected-(U1-PB0(ICP)-Pad12)") (class "Default")
      (node (ref "U1") (pin "12") (pinfunction "PB0(ICP)_12") (pintype "bidirectional"))
    )
    (net (code "149") (name "unconnected-(U1-PC1(ADC1)-Pad24)") (class "Default")
      (node (ref "U1") (pin "24") (pinfunction "PC1(ADC1)_24") (pintype "bidirectional"))
    )
    (net (code "150") (name "unconnected-(U1-PC2(ADC2)-Pad25)") (class "Default")
      (node (ref "U1") (pin "25") (pinfunction "PC2(ADC2)_25") (pintype "bidirectional"))
    )
    (net (code "151") (name "unconnected-(U1-PC3(ADC3)-Pad26)") (class "Default")
      (node (ref "U1") (pin "26") (pinfunction "PC3(ADC3)_26") (pintype "bidirectional"))
    )
    (net (code "152") (name "unconnected-(U1-PC4(ADC4{slash}SDA)-Pad27)") (class "Default")
      (node (ref "U1") (pin "27") (pinfunction "PC4(ADC4/SDA)_27") (pintype "bidirectional"))
    )
    (net (code "153") (name "unconnected-(U1-PC5(ADC5{slash}SCL)-Pad28)") (class "Default")
      (node (ref "U1") (pin "28") (pinfunction "PC5(ADC5/SCL)_28") (pintype "bidirectional"))
    )
    (net (code "154") (name "unconnected-(U1-PD2(INT0)-Pad32)") (class "Default")
      (node (ref "U1") (pin "32") (pinfunction "PD2(INT0)_32") (pintype "bidirectional"))
    )
    (net (code "155") (name "unconnected-(U1-PD3(INT1)-Pad1)") (class "Default")
      (node (ref "U1") (pin "1") (pinfunction "PD3(INT1)_1") (pintype "bidirectional"))
    )
    (net (code "156") (name "unconnected-(U1-PD4(XCK{slash}T0)-Pad2)") (class "Default")
      (node (ref "U1") (pin "2") (pinfunction "PD4(XCK/T0)_2") (pintype "bidirectional"))
    )
    (net (code "157") (name "unconnected-(U1-PD5(T1)-Pad9)") (class "Default")
      (node (ref "U1") (pin "9") (pinfunction "PD5(T1)_9") (pintype "bidirectional"))
    )
    (net (code "158") (name "unconnected-(U1-PD6(AIN0)-Pad10)") (class "Default")
      (node (ref "U1") (pin "10") (pinfunction "PD6(AIN0)_10") (pintype "bidirectional"))
    )
    (net (code "159") (name "unconnected-(U1-PD7(AIN1)-Pad11)") (class "Default")
      (node (ref "U1") (pin "11") (pinfunction "PD7(AIN1)_11") (pintype "bidirectional"))
    )
    (net (code "160") (name "unconnected-(U2-NC-Pad34)") (class "Default")
      (node (ref "U2") (pin "34") (pinfunction "NC_34") (pintype "no_connect"))
    )
    (net (code "161") (name "unconnected-(U2-NC_2-Pad12)") (class "Default")
      (node (ref "U2") (pin "12") (pinfunction "NC_2_12") (pintype "no_connect"))
    )
    (net (code "162") (name "unconnected-(U2-NC_3-Pad13)") (class "Default")
      (node (ref "U2") (pin "13") (pinfunction "NC_3_13") (pintype "no_connect"))
    )
    (net (code "163") (name "unconnected-(U2-NC_4-Pad33)") (class "Default")
      (node (ref "U2") (pin "33") (pinfunction "NC_4_33") (pintype "no_connect"))
    )
  )
)
